# permamote.net
KiCad netlist of a schematic drawn in EAGLE
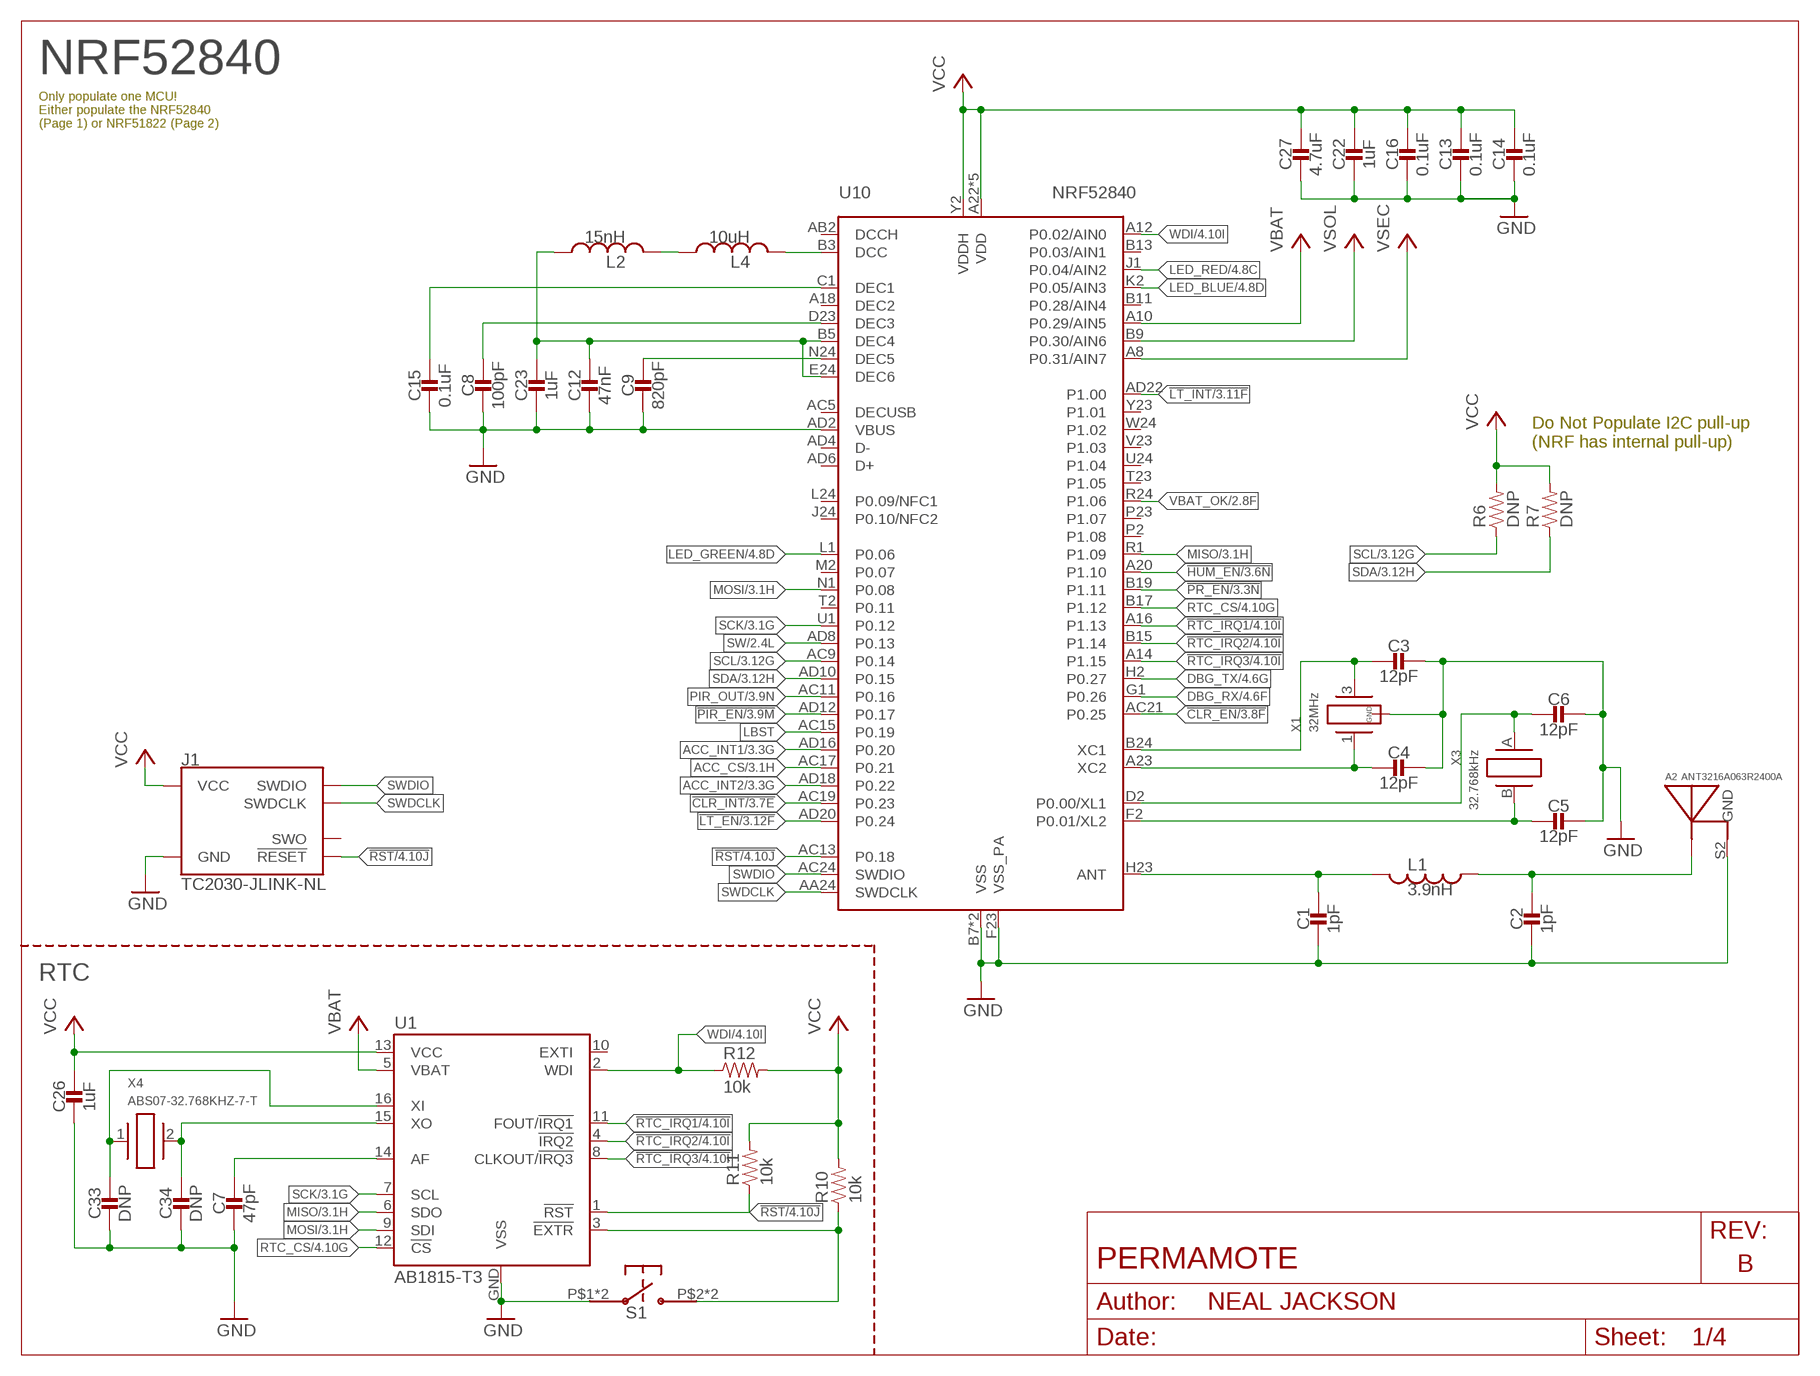
[diagram p0: schematic, sheet 1]
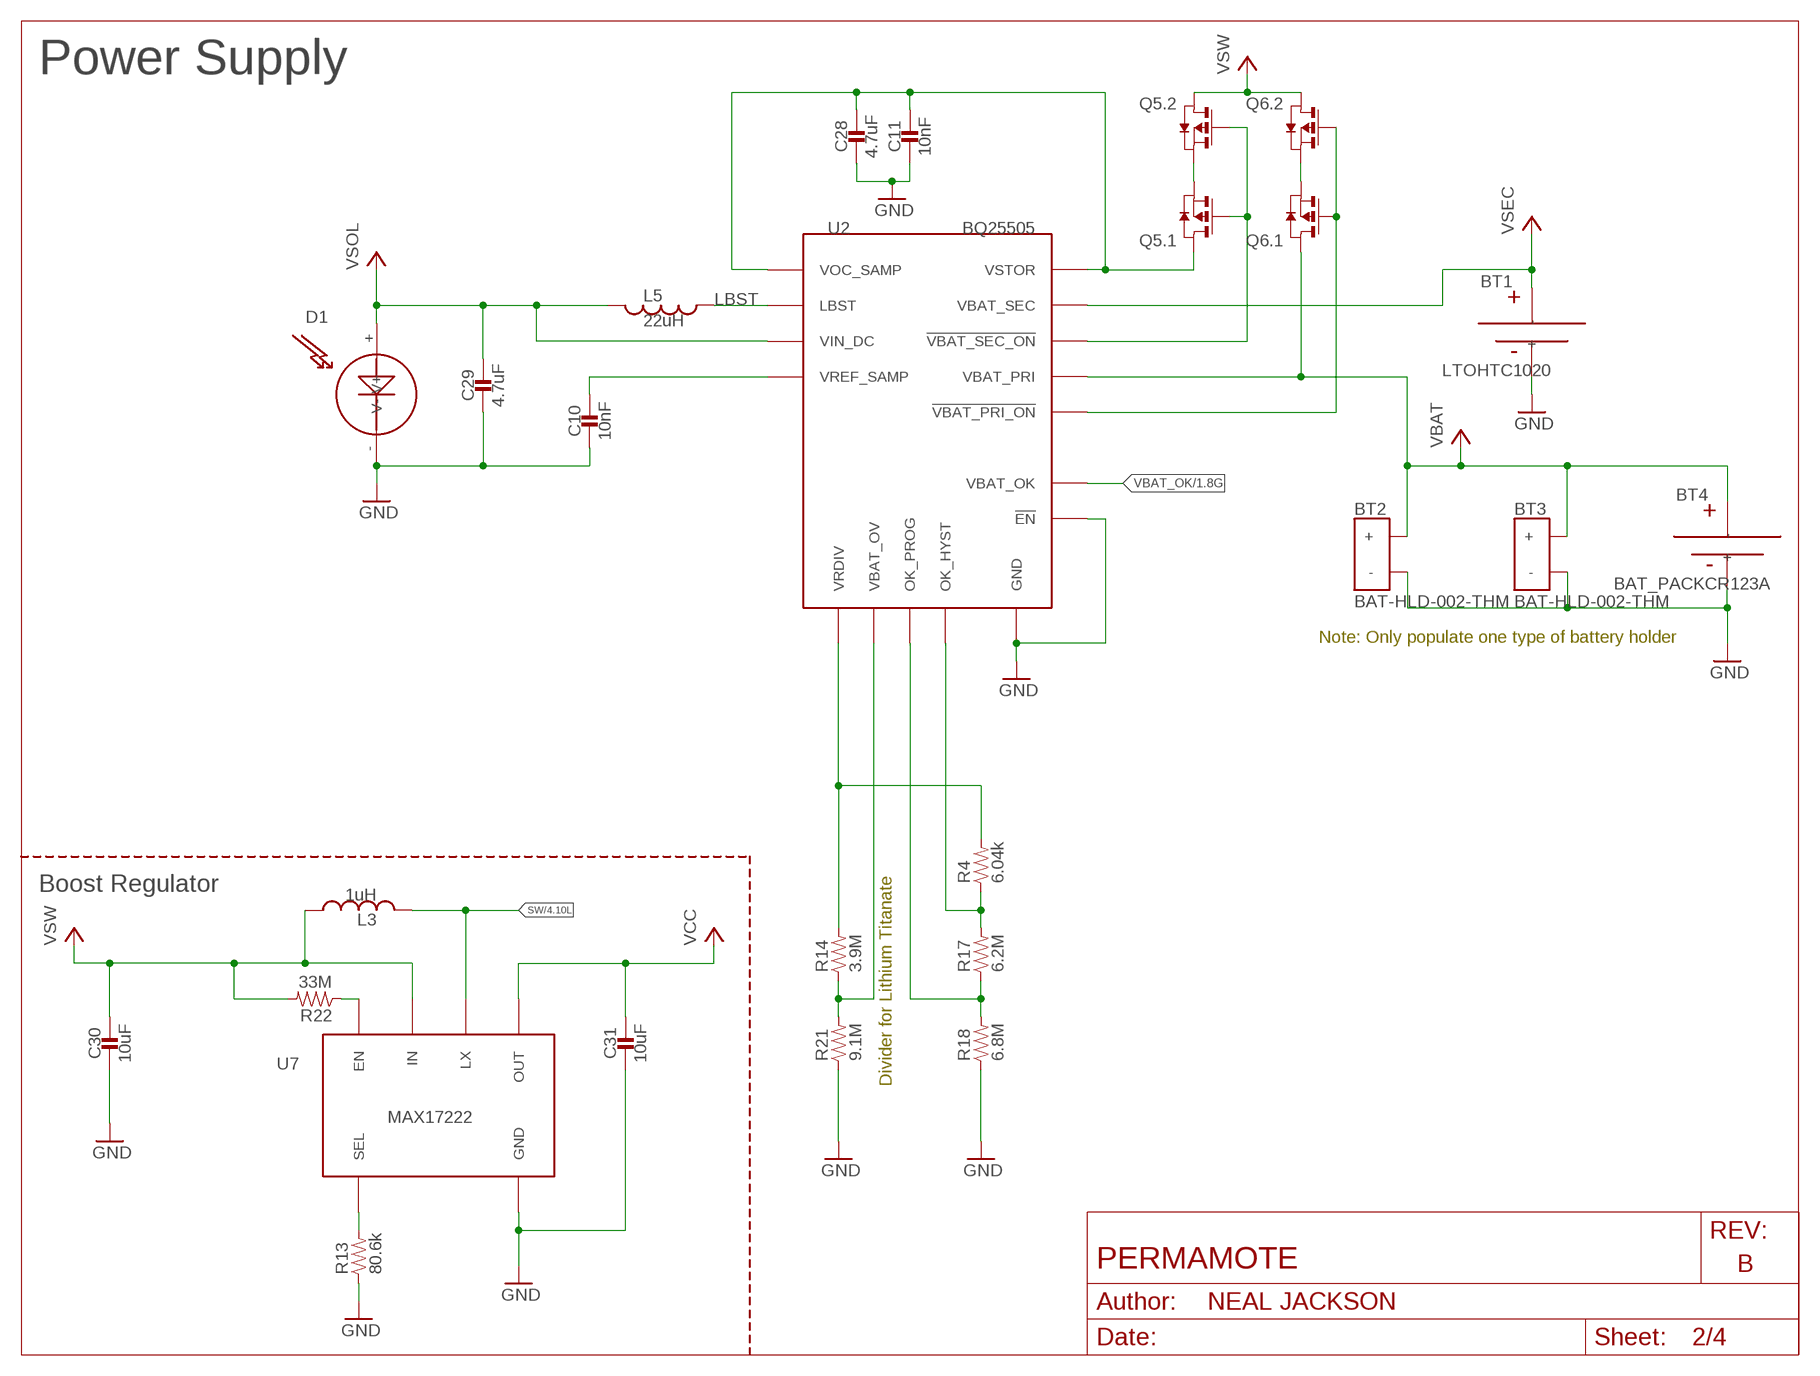
[diagram p1: schematic, sheet 2]
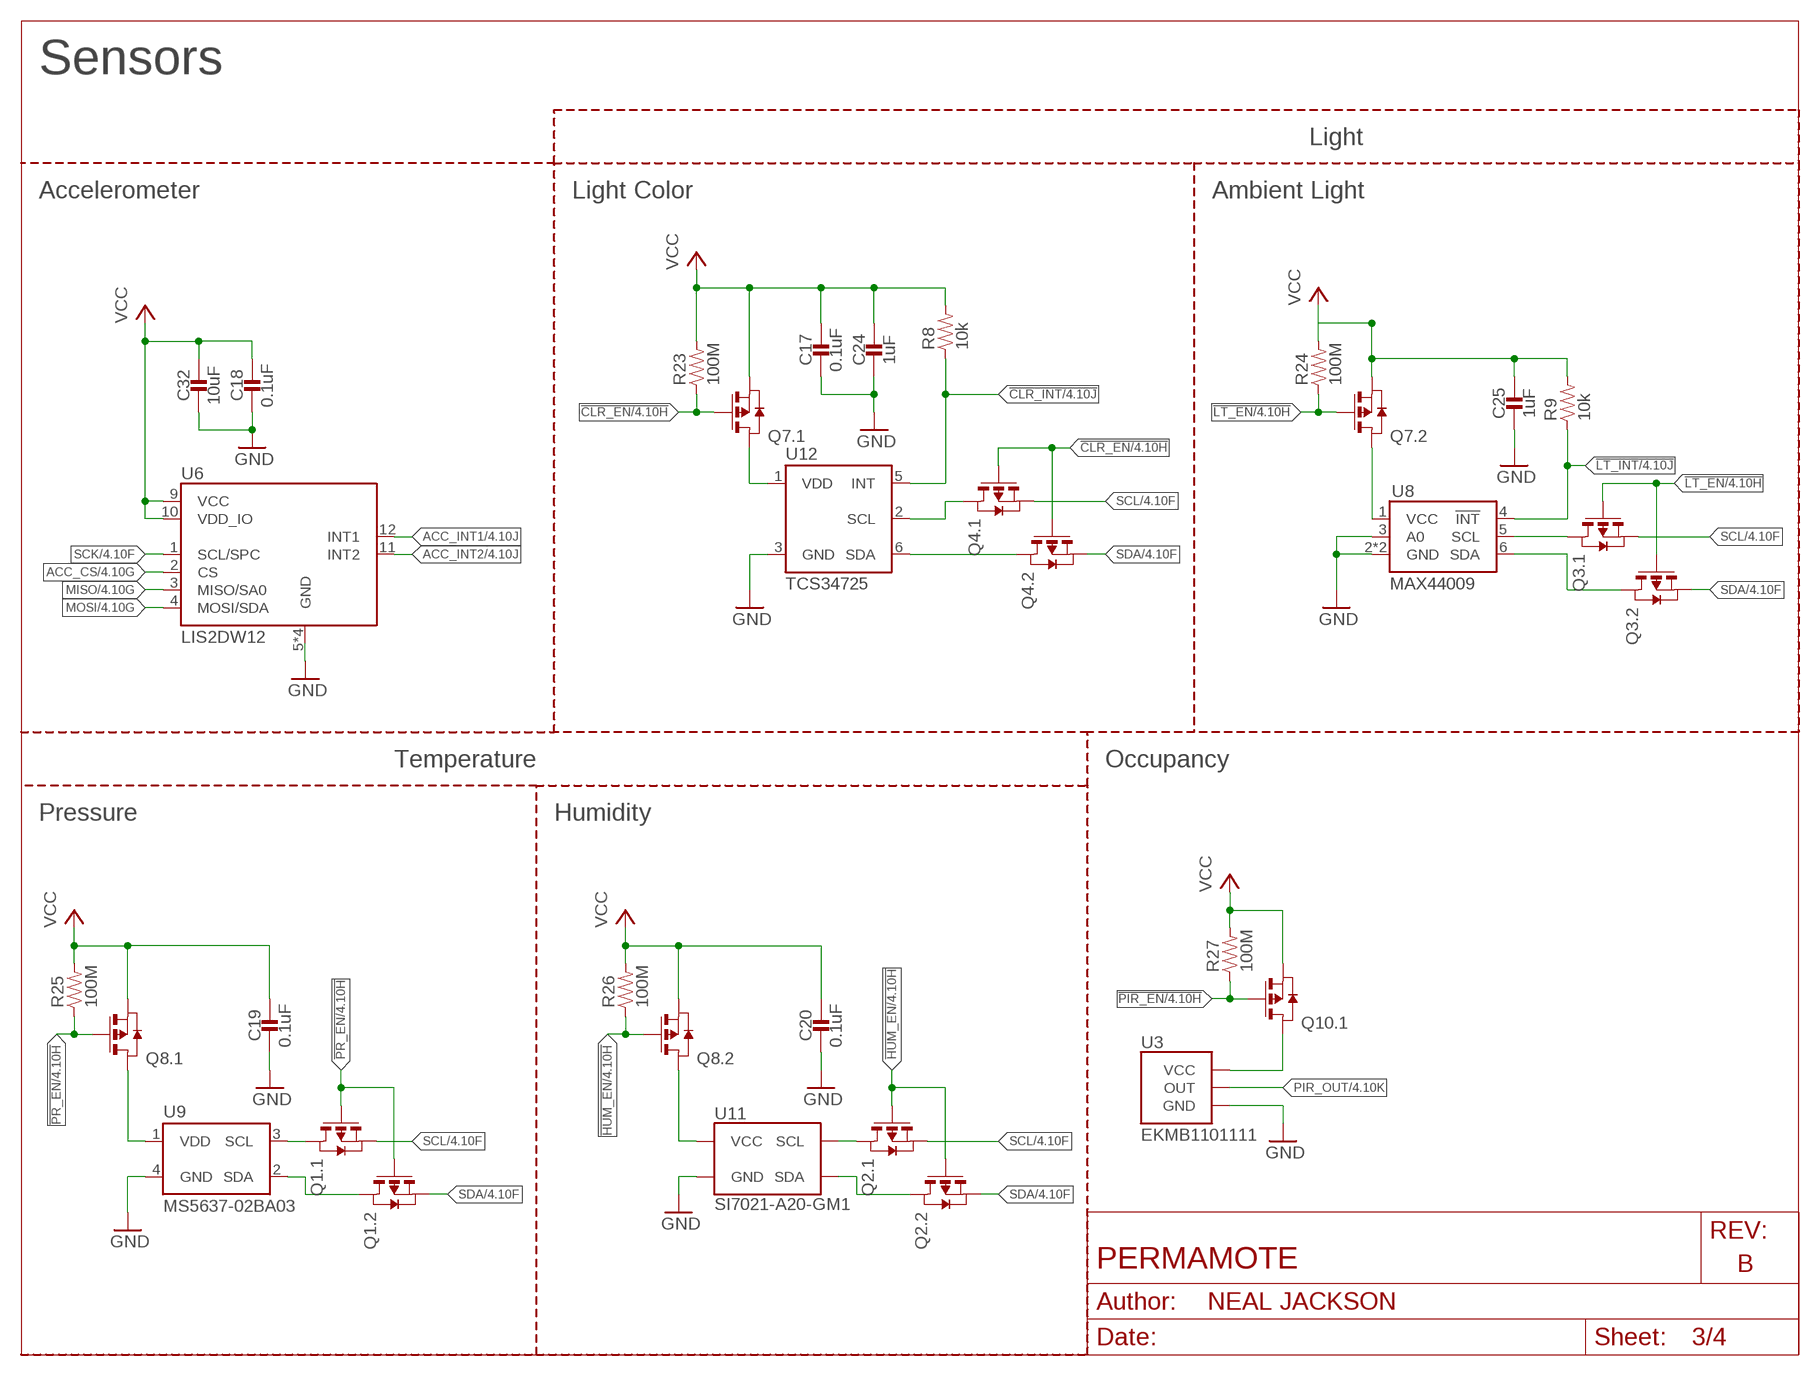
[diagram p2: schematic, sheet 3]
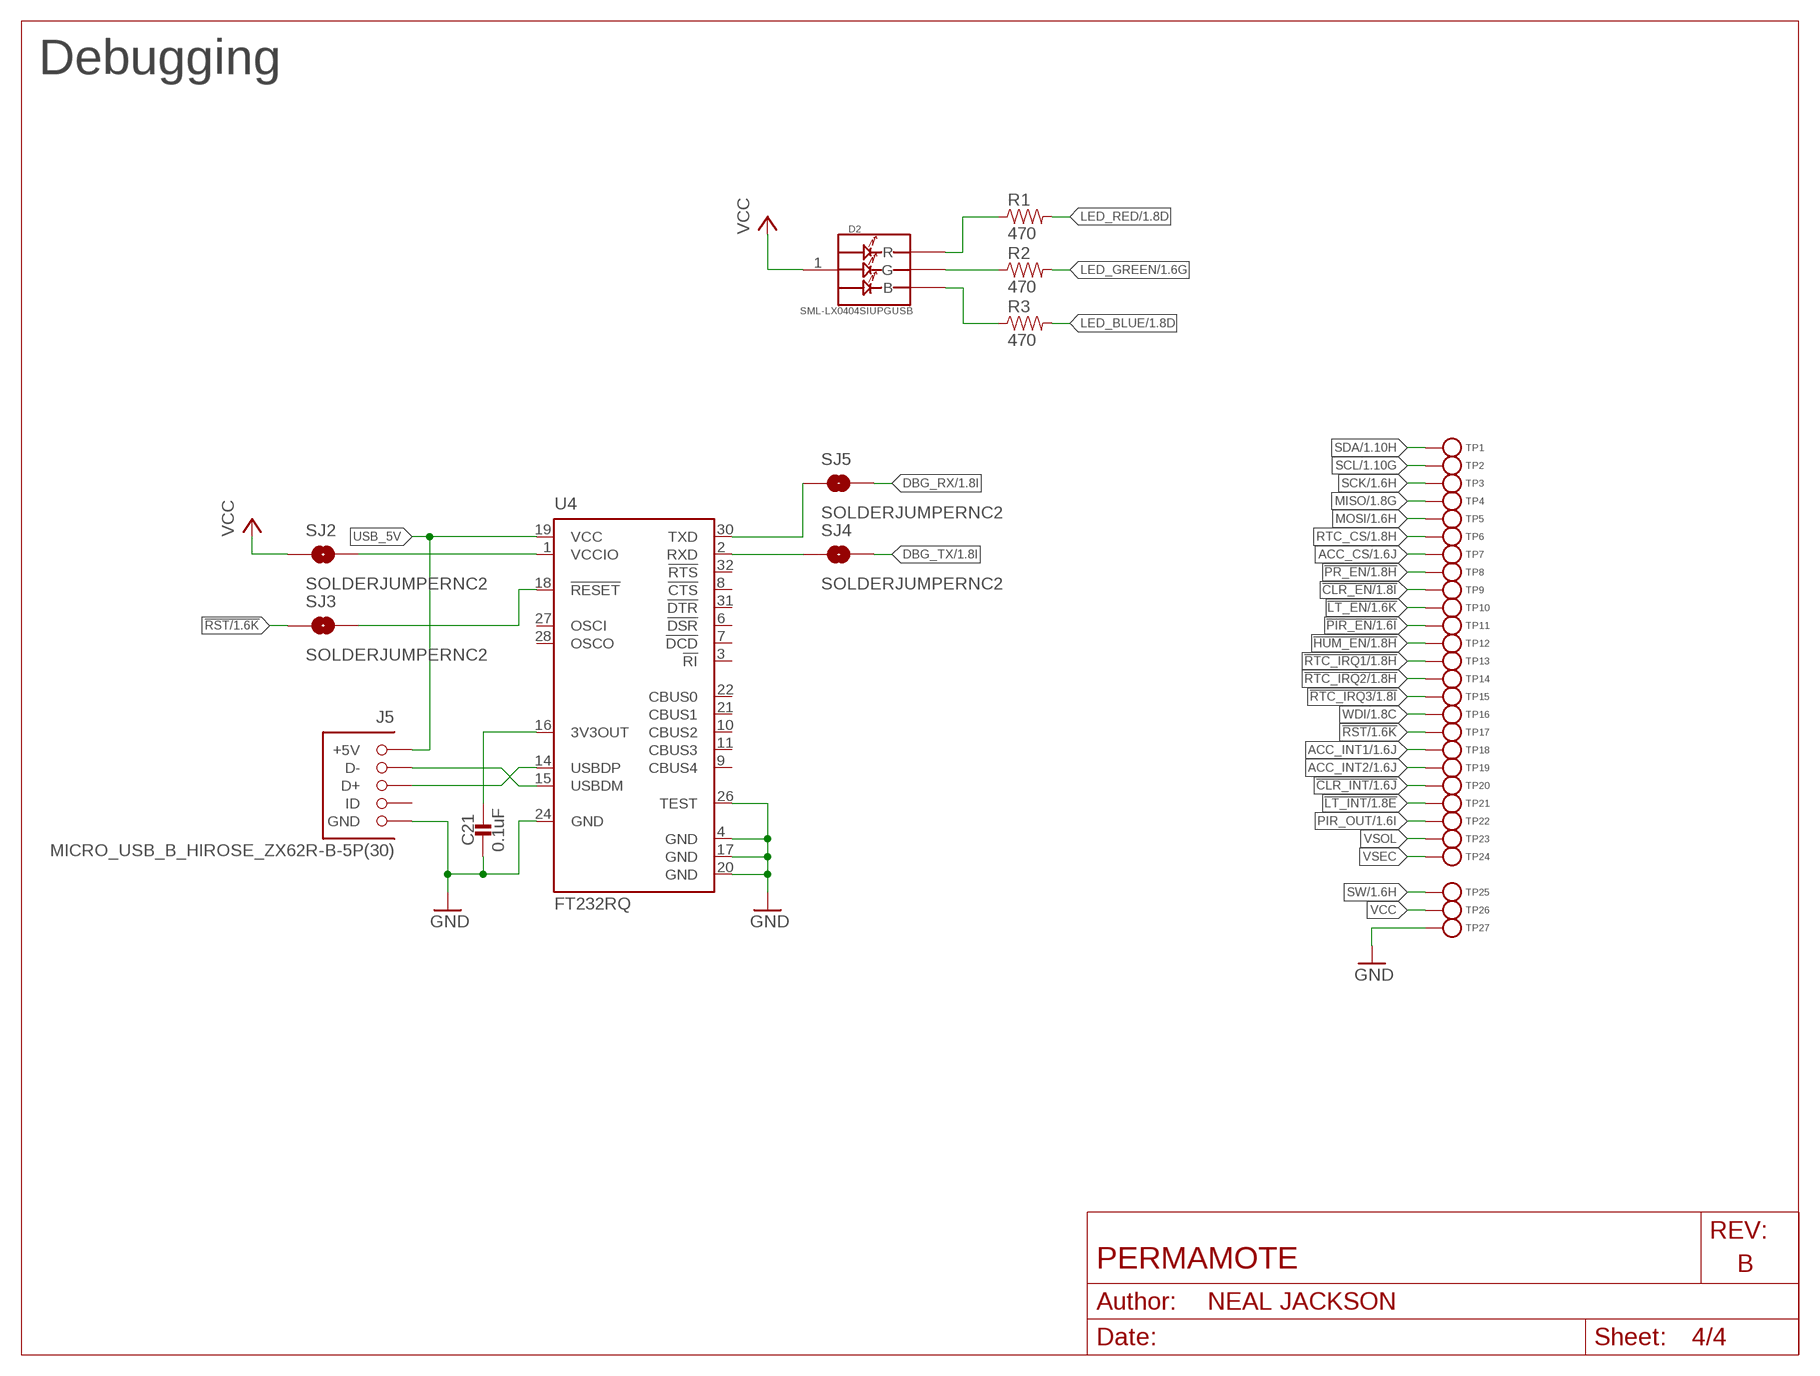
[diagram p3: schematic, sheet 4]

(export (version "E")
  (design (tool "Eeschema 10.0.6"))
  (components
    (comp (ref "A2")
      (value "ANT3216A063R2400A")
      (footprint "eagle-import:ANT3216A063R2400A")
      (fields (field (name "MANUFACTURER") "YAGEO"))
      (libsource (lib "eagle-import") (part "ANT3216A063R2400A"))
    )
    (comp (ref "C1")
      (value "1pF")
      (footprint "eagle-import:0402_CAP")
      (fields (field (name "MPN") "CL05C010CB5NNNC"))
      (libsource (lib "eagle-import") (part "CAPACITOR0402_CAP"))
    )
    (comp (ref "C2")
      (value "1pF")
      (footprint "eagle-import:0402_CAP")
      (fields (field (name "MPN") "CL05C010CB5NNNC"))
      (libsource (lib "eagle-import") (part "CAPACITOR0402_CAP"))
    )
    (comp (ref "C3")
      (value "12pF")
      (footprint "eagle-import:0402_CAP")
      (fields (field (name "MPN") "GRM1555C1H120GA01D "))
      (libsource (lib "eagle-import") (part "CAPACITOR0402_CAP"))
    )
    (comp (ref "C4")
      (value "12pF")
      (footprint "eagle-import:0402_CAP")
      (fields (field (name "MPN") "GRM1555C1H120GA01D "))
      (libsource (lib "eagle-import") (part "CAPACITOR0402_CAP"))
    )
    (comp (ref "C5")
      (value "12pF")
      (footprint "eagle-import:0402_CAP")
      (fields (field (name "MPN") "GRM1555C1H120GA01D "))
      (libsource (lib "eagle-import") (part "CAPACITOR0402_CAP"))
    )
    (comp (ref "C6")
      (value "12pF")
      (footprint "eagle-import:0402_CAP")
      (fields (field (name "MPN") "GRM1555C1H120GA01D "))
      (libsource (lib "eagle-import") (part "CAPACITOR0402_CAP"))
    )
    (comp (ref "C7")
      (value "47pF")
      (footprint "eagle-import:0402_CAP")
      (fields (field (name "MPN") "GRM1555C1H470JA01D "))
      (libsource (lib "eagle-import") (part "CAPACITOR0402_CAP"))
    )
    (comp (ref "C8")
      (value "100pF")
      (footprint "eagle-import:0402_CAP")
      (fields (field (name "MPN") "GRM1555C1H101JA01D "))
      (libsource (lib "eagle-import") (part "CAPACITOR0402_CAP"))
    )
    (comp (ref "C9")
      (value "820pF")
      (footprint "eagle-import:0402_CAP")
      (fields (field (name "MPN") "CL05B821KO5NNNC"))
      (libsource (lib "eagle-import") (part "CAPACITOR0402_CAP"))
    )
    (comp (ref "C12")
      (value "47nF")
      (footprint "eagle-import:0402_CAP")
      (fields (field (name "MPN") "C1005X7R1C473K050BC "))
      (libsource (lib "eagle-import") (part "CAPACITOR0402_CAP"))
    )
    (comp (ref "C13")
      (value "0.1uF")
      (footprint "eagle-import:0402_CAP")
      (fields (field (name "MPN") "GRM155R71C104KA88J "))
      (libsource (lib "eagle-import") (part "CAPACITOR0402_CAP"))
    )
    (comp (ref "C14")
      (value "0.1uF")
      (footprint "eagle-import:0402_CAP")
      (fields (field (name "MPN") "GRM155R71C104KA88J "))
      (libsource (lib "eagle-import") (part "CAPACITOR0402_CAP"))
    )
    (comp (ref "C15")
      (value "0.1uF")
      (footprint "eagle-import:0402_CAP")
      (fields (field (name "MPN") "GRM155R71C104KA88J "))
      (libsource (lib "eagle-import") (part "CAPACITOR0402_CAP"))
    )
    (comp (ref "C16")
      (value "0.1uF")
      (footprint "eagle-import:0402_CAP")
      (fields (field (name "MPN") "GRM155R71C104KA88J "))
      (libsource (lib "eagle-import") (part "CAPACITOR0402_CAP"))
    )
    (comp (ref "C22")
      (value "1uF")
      (footprint "eagle-import:0402_CAP")
      (fields (field (name "MPN") "GRM155R70G105KA12D "))
      (libsource (lib "eagle-import") (part "CAPACITOR0402_CAP"))
    )
    (comp (ref "C23")
      (value "1uF")
      (footprint "eagle-import:0402_CAP")
      (fields (field (name "MPN") "GRM155R70G105KA12D "))
      (libsource (lib "eagle-import") (part "CAPACITOR0402_CAP"))
    )
    (comp (ref "C26")
      (value "1uF")
      (footprint "eagle-import:0402_CAP")
      (fields (field (name "MPN") "GRM155R70G105KA12D "))
      (libsource (lib "eagle-import") (part "CAPACITOR0402_CAP"))
    )
    (comp (ref "C27")
      (value "4.7uF")
      (footprint "eagle-import:0402_CAP")
      (fields (field (name "MPN") "C1005X5R0J475K050BC "))
      (libsource (lib "eagle-import") (part "CAPACITOR0402_CAP"))
    )
    (comp (ref "C33")
      (value "DNP")
      (footprint "eagle-import:0402_CAP")
      (libsource (lib "eagle-import") (part "CAPACITOR0402_CAP"))
    )
    (comp (ref "C34")
      (value "DNP")
      (footprint "eagle-import:0402_CAP")
      (libsource (lib "eagle-import") (part "CAPACITOR0402_CAP"))
    )
    (comp (ref "J1")
      (value "TC2030-JLINK-NL")
      (footprint "eagle-import:TC2030-IDC-NL")
      (libsource (lib "eagle-import") (part "TC2030-JLINK-NL"))
    )
    (comp (ref "L1")
      (value "3.9nH")
      (footprint "eagle-import:0402_CAP")
      (fields (field (name "MPN") "LQP15MN3N9B02D"))
      (libsource (lib "eagle-import") (part "INDUCTOR0402"))
    )
    (comp (ref "L2")
      (value "15nH")
      (footprint "eagle-import:0402_CAP")
      (fields (field (name "MPN") "HK100515NJ-T "))
      (libsource (lib "eagle-import") (part "INDUCTOR0402"))
    )
    (comp (ref "L4")
      (value "10uH")
      (footprint "eagle-import:0603_CAP")
      (fields (field (name "MPN") "LQM18FN100M00D "))
      (libsource (lib "eagle-import") (part "INDUCTOR0603"))
    )
    (comp (ref "R6")
      (value "DNP")
      (footprint "eagle-import:0402_RES")
      (fields (field (name "MPN") "RC0402JR-0710KL"))
      (libsource (lib "eagle-import") (part "RESISTOR0402_RES"))
    )
    (comp (ref "R7")
      (value "DNP")
      (footprint "eagle-import:0402_RES")
      (fields (field (name "MPN") "RC0402JR-0710KL"))
      (libsource (lib "eagle-import") (part "RESISTOR0402_RES"))
    )
    (comp (ref "R10")
      (value "10k")
      (footprint "eagle-import:0402_RES")
      (fields (field (name "MPN") "RC0402JR-0710KL"))
      (libsource (lib "eagle-import") (part "RESISTOR0402_RES"))
    )
    (comp (ref "R11")
      (value "10k")
      (footprint "eagle-import:0402_RES")
      (fields (field (name "MPN") "RC0402JR-0710KL"))
      (libsource (lib "eagle-import") (part "RESISTOR0402_RES"))
    )
    (comp (ref "R12")
      (value "10k")
      (footprint "eagle-import:0402_RES")
      (fields (field (name "MPN") "RC0402JR-0710KL"))
      (libsource (lib "eagle-import") (part "RESISTOR0402_RES"))
    )
    (comp (ref "S1")
      (value "EVQP2")
      (footprint "eagle-import:EVQP2")
      (fields (field (name "MPN") "EVQ-P2K02Q "))
      (libsource (lib "eagle-import") (part "EVQP2"))
    )
    (comp (ref "U1")
      (value "AB1815-T3")
      (footprint "eagle-import:QFN-16-3MM")
      (fields (field (name "MANUFACTURER") "Abracon"))
      (libsource (lib "eagle-import") (part "AB1815-T3"))
    )
    (comp (ref "U10")
      (value "NRF52840")
      (footprint "eagle-import:AQFN73")
      (fields (field (name "MANUFACTURER") "NORIDIC SEMICONDUCTOR"))
      (libsource (lib "eagle-import") (part "NRF52840"))
    )
    (comp (ref "X1")
      (value "32MHz")
      (footprint "eagle-import:TXC-7V")
      (fields (field (name "MANUFACTURER") "TXC CORPORATION") (field (name "MPN") "7M-32.000MAHV-T"))
      (libsource (lib "eagle-import") (part "7V-32.000MAHV-T"))
    )
    (comp (ref "X3")
      (value "32.768kHz")
      (footprint "eagle-import:ABS05")
      (fields (field (name "MANUFACTURER") "Abracon") (field (name "MPN") "ABS05-32.768KHZ-9-T"))
      (libsource (lib "eagle-import") (part "ABS05-32.768KHZ-9-T"))
    )
    (comp (ref "X4")
      (value "ABS07-32.768KHZ-7-T")
      (footprint "eagle-import:2-SMD")
      (fields (field (name "MANUFACTURER") "ABRACON") (field (name "MPN") "ABS07-32.768KHZ-7-T "))
      (libsource (lib "eagle-import") (part "ABS07-32.768KHZ-7-T"))
    )
    (comp (ref "BT1")
      (value "LTOHTC1020")
      (footprint "eagle-import:1020")
      (libsource (lib "eagle-import") (part "LTOHTC1020"))
    )
    (comp (ref "BT2")
      (value "BAT-HLD-002-THM")
      (footprint "eagle-import:BAT-HLD-002-THM")
      (fields
        (field (name "DIGIKEY") "BAT-HLD-001-THM-ND")
        (field (name "MOUSER") "712-BAT-HLD-001-THM")
        (field (name "MPN") "BAT-HLD-001-THM")
      )
      (libsource (lib "eagle-import") (part "BAT-HLD-002-THM"))
    )
    (comp (ref "BT3")
      (value "BAT-HLD-002-THM")
      (footprint "eagle-import:BAT-HLD-002-THM")
      (fields
        (field (name "DIGIKEY") "BAT-HLD-001-THM-ND")
        (field (name "MOUSER") "712-BAT-HLD-001-THM")
        (field (name "MPN") "BAT-HLD-001-THM")
      )
      (libsource (lib "eagle-import") (part "BAT-HLD-002-THM"))
    )
    (comp (ref "BT4")
      (value "BAT_PACKCR123A")
      (footprint "eagle-import:BH123A")
      (fields (field (name "MANUFACTURER") "MPD") (field (name "MPN") "BH123A"))
      (libsource (lib "eagle-import") (part "BAT_PACKCR123A"))
    )
    (comp (ref "C10")
      (value "10nF")
      (footprint "eagle-import:0402_CAP")
      (fields (field (name "MPN") "GRM155R71H103KA88D "))
      (libsource (lib "eagle-import") (part "CAPACITOR0402_CAP"))
    )
    (comp (ref "C11")
      (value "10nF")
      (footprint "eagle-import:0402_CAP")
      (fields (field (name "MPN") "GRM155R71H103KA88D "))
      (libsource (lib "eagle-import") (part "CAPACITOR0402_CAP"))
    )
    (comp (ref "C28")
      (value "4.7uF")
      (footprint "eagle-import:0402_CAP")
      (fields (field (name "MPN") "C1005X5R0J475K050BC "))
      (libsource (lib "eagle-import") (part "CAPACITOR0402_CAP"))
    )
    (comp (ref "C29")
      (value "4.7uF")
      (footprint "eagle-import:0402_CAP")
      (fields (field (name "MPN") "C1005X5R0J475K050BC "))
      (libsource (lib "eagle-import") (part "CAPACITOR0402_CAP"))
    )
    (comp (ref "C30")
      (value "10uF")
      (footprint "eagle-import:0603_CAP")
      (fields (field (name "MPN") "GRM188R60J106ME47D "))
      (libsource (lib "eagle-import") (part "CAPACITOR0603_CAP"))
    )
    (comp (ref "C31")
      (value "10uF")
      (footprint "eagle-import:0603_CAP")
      (fields (field (name "MPN") "GRM188R60J106ME47D "))
      (libsource (lib "eagle-import") (part "CAPACITOR0603_CAP"))
    )
    (comp (ref "D1")
      (value "SOLARCELLHOLES")
      (footprint "eagle-import:SOLAR_HOLES")
      (fields (field (name "MPN") "AM-1454CA"))
      (libsource (lib "eagle-import") (part "SOLARCELLHOLES"))
    )
    (comp (ref "L3")
      (value "1uH")
      (footprint "eagle-import:IHL-1212BZ-11")
      (fields
        (field (name "MANUFACTURER") "Vishay Dale")
        (field (name "MPN") "IHLP1212BZER2R2M11")
        (field (name "DIGIKEY") "541-1319-1-ND")
        (field (name "MPN_1") "IHLP1212BZER1R0M11")
      )
      (libsource (lib "eagle-import") (part "INDUCTORIHL"))
    )
    (comp (ref "L5")
      (value "22uH")
      (footprint "eagle-import:74437324220")
      (fields (field (name "DIGIKEY") "732-3340-1-ND") (field (name "MPN") "74437324220 "))
      (libsource (lib "eagle-import") (part "INDUCTOR74437324220"))
    )
    (comp (ref "Q5")
      (value "PMDXB950UPEL")
      (footprint "eagle-import:XDFN-6")
      (fields (field (name "MANUFACTURER") "NEXPERIA") (field (name "MPN") "PMDXB950UPELZ"))
      (libsource (lib "eagle-import") (part "PMDXB950UPEL"))
    )
    (comp (ref "Q6")
      (value "PMDXB950UPEL")
      (footprint "eagle-import:XDFN-6")
      (fields (field (name "MANUFACTURER") "NEXPERIA") (field (name "MPN") "PMDXB950UPELZ"))
      (libsource (lib "eagle-import") (part "PMDXB950UPEL"))
    )
    (comp (ref "R4")
      (value "6.04k")
      (footprint "eagle-import:0402_RES")
      (fields (field (name "MPN") "RC0402FR-076K04L"))
      (libsource (lib "eagle-import") (part "RESISTOR0402_RES"))
    )
    (comp (ref "R13")
      (value "80.6k")
      (footprint "eagle-import:0603-RES")
      (fields (field (name "MPN") "RC0603FR-0780K6L "))
      (libsource (lib "eagle-import") (part "RESISTOR0603_RES"))
    )
    (comp (ref "R14")
      (value "3.9M")
      (footprint "eagle-import:0402_RES")
      (fields (field (name "MPN") "RC0402JR-073M9L"))
      (libsource (lib "eagle-import") (part "RESISTOR0402_RES"))
    )
    (comp (ref "R17")
      (value "6.2M")
      (footprint "eagle-import:0402_RES")
      (fields (field (name "MPN") "RC0402JR-076M2L"))
      (libsource (lib "eagle-import") (part "RESISTOR0402_RES"))
    )
    (comp (ref "R18")
      (value "6.8M")
      (footprint "eagle-import:0402_RES")
      (fields (field (name "MPN") "RC0402JR-076M8L"))
      (libsource (lib "eagle-import") (part "RESISTOR0402_RES"))
    )
    (comp (ref "R21")
      (value "9.1M")
      (footprint "eagle-import:0402_RES")
      (fields (field (name "MPN") "RC0402JR-079M1L"))
      (libsource (lib "eagle-import") (part "RESISTOR0402_RES"))
    )
    (comp (ref "R22")
      (value "33M")
      (footprint "eagle-import:0603-RES")
      (fields (field (name "MPN") "HMC0603JT33M0 "))
      (libsource (lib "eagle-import") (part "RESISTOR0603_RES"))
    )
    (comp (ref "U2")
      (value "BQ25505")
      (footprint "eagle-import:S-PVQFN-N20-RGR")
      (fields (field (name "MANUFACTURER") "TI") (field (name "MPN") "BQ25505RGRR"))
      (libsource (lib "eagle-import") (part "BQ25505"))
    )
    (comp (ref "U7")
      (value "MAX17222")
      (footprint "eagle-import:UDFN-6-MAXIM")
      (fields (field (name "MANUFACTURER") "MAXIM INTEGRATED") (field (name "MPN") "MAX17222ELT+T"))
      (libsource (lib "eagle-import") (part "MAX17222"))
    )
    (comp (ref "C17")
      (value "0.1uF")
      (footprint "eagle-import:0402_CAP")
      (fields (field (name "MPN") "GRM155R71C104KA88J "))
      (libsource (lib "eagle-import") (part "CAPACITOR0402_CAP"))
    )
    (comp (ref "C18")
      (value "0.1uF")
      (footprint "eagle-import:0402_CAP")
      (fields (field (name "MPN") "GRM155R71C104KA88J "))
      (libsource (lib "eagle-import") (part "CAPACITOR0402_CAP"))
    )
    (comp (ref "C19")
      (value "0.1uF")
      (footprint "eagle-import:0402_CAP")
      (fields (field (name "MPN") "GRM155R71C104KA88J "))
      (libsource (lib "eagle-import") (part "CAPACITOR0402_CAP"))
    )
    (comp (ref "C20")
      (value "0.1uF")
      (footprint "eagle-import:0402_CAP")
      (fields (field (name "MPN") "GRM155R71C104KA88J "))
      (libsource (lib "eagle-import") (part "CAPACITOR0402_CAP"))
    )
    (comp (ref "C24")
      (value "1uF")
      (footprint "eagle-import:0402_CAP")
      (fields (field (name "MPN") "GRM155R70G105KA12D "))
      (libsource (lib "eagle-import") (part "CAPACITOR0402_CAP"))
    )
    (comp (ref "C25")
      (value "1uF")
      (footprint "eagle-import:0402_CAP")
      (fields (field (name "MPN") "GRM155R70G105KA12D "))
      (libsource (lib "eagle-import") (part "CAPACITOR0402_CAP"))
    )
    (comp (ref "C32")
      (value "10uF")
      (footprint "eagle-import:0603_CAP")
      (fields (field (name "MPN") "GRM188R60J106ME47D "))
      (libsource (lib "eagle-import") (part "CAPACITOR0603_CAP"))
    )
    (comp (ref "Q1")
      (value "PMDXB950UPEL")
      (footprint "eagle-import:XDFN-6")
      (fields (field (name "MANUFACTURER") "NEXPERIA") (field (name "MPN") "PMDXB950UPELZ"))
      (libsource (lib "eagle-import") (part "PMDXB950UPEL"))
    )
    (comp (ref "Q2")
      (value "PMDXB950UPEL")
      (footprint "eagle-import:XDFN-6")
      (fields (field (name "MANUFACTURER") "NEXPERIA") (field (name "MPN") "PMDXB950UPELZ"))
      (libsource (lib "eagle-import") (part "PMDXB950UPEL"))
    )
    (comp (ref "Q3")
      (value "PMDXB950UPEL")
      (footprint "eagle-import:XDFN-6")
      (fields (field (name "MANUFACTURER") "NEXPERIA") (field (name "MPN") "PMDXB950UPELZ"))
      (libsource (lib "eagle-import") (part "PMDXB950UPEL"))
    )
    (comp (ref "Q4")
      (value "PMDXB950UPEL")
      (footprint "eagle-import:XDFN-6")
      (fields (field (name "MANUFACTURER") "NEXPERIA") (field (name "MPN") "PMDXB950UPELZ"))
      (libsource (lib "eagle-import") (part "PMDXB950UPEL"))
    )
    (comp (ref "Q7")
      (value "PMDXB950UPEL")
      (footprint "eagle-import:XDFN-6")
      (fields (field (name "MANUFACTURER") "NEXPERIA") (field (name "MPN") "PMDXB950UPELZ"))
      (libsource (lib "eagle-import") (part "PMDXB950UPEL"))
    )
    (comp (ref "Q8")
      (value "PMDXB950UPEL")
      (footprint "eagle-import:XDFN-6")
      (fields (field (name "MANUFACTURER") "NEXPERIA") (field (name "MPN") "PMDXB950UPELZ"))
      (libsource (lib "eagle-import") (part "PMDXB950UPEL"))
    )
    (comp (ref "Q10")
      (value "PMDXB950UPEL")
      (footprint "eagle-import:XDFN-6")
      (fields (field (name "MANUFACTURER") "NEXPERIA") (field (name "MPN") "PMDXB950UPELZ"))
      (libsource (lib "eagle-import") (part "PMDXB950UPEL"))
    )
    (comp (ref "R8")
      (value "10k")
      (footprint "eagle-import:0402_RES")
      (fields (field (name "MPN") "RC0402JR-0710KL"))
      (libsource (lib "eagle-import") (part "RESISTOR0402_RES"))
    )
    (comp (ref "R9")
      (value "10k")
      (footprint "eagle-import:0402_RES")
      (fields (field (name "MPN") "RC0402JR-0710KL"))
      (libsource (lib "eagle-import") (part "RESISTOR0402_RES"))
    )
    (comp (ref "R23")
      (value "100M")
      (footprint "eagle-import:0402_RES")
      (fields (field (name "MPN") "HMC0402JT100M "))
      (libsource (lib "eagle-import") (part "RESISTOR0402_RES"))
    )
    (comp (ref "R24")
      (value "100M")
      (footprint "eagle-import:0402_RES")
      (fields (field (name "MPN") "HMC0402JT100M "))
      (libsource (lib "eagle-import") (part "RESISTOR0402_RES"))
    )
    (comp (ref "R25")
      (value "100M")
      (footprint "eagle-import:0402_RES")
      (fields (field (name "MPN") "HMC0402JT100M "))
      (libsource (lib "eagle-import") (part "RESISTOR0402_RES"))
    )
    (comp (ref "R26")
      (value "100M")
      (footprint "eagle-import:0402_RES")
      (fields (field (name "MPN") "HMC0402JT100M "))
      (libsource (lib "eagle-import") (part "RESISTOR0402_RES"))
    )
    (comp (ref "R27")
      (value "100M")
      (footprint "eagle-import:0402_RES")
      (fields (field (name "MPN") "HMC0402JT100M "))
      (libsource (lib "eagle-import") (part "RESISTOR0402_RES"))
    )
    (comp (ref "U3")
      (value "EKMB1101111")
      (footprint "eagle-import:AMN2")
      (fields (field (name "MANUFACTURER") "PANASONIC"))
      (libsource (lib "eagle-import") (part "EKMB1101111"))
    )
    (comp (ref "U6")
      (value "LIS2DW12")
      (footprint "eagle-import:LGA-12")
      (fields (field (name "MANUFACTURER") "STMicroelectronics") (field (name "MPN") "LIS2DW12TR"))
      (libsource (lib "eagle-import") (part "LIS2DW12"))
    )
    (comp (ref "U8")
      (value "MAX44009")
      (footprint "eagle-import:UDFN-6-EXPOSED")
      (fields (field (name "MANUFACTURER") "MAXIM") (field (name "MPN") "MAX44009EDT+T"))
      (libsource (lib "eagle-import") (part "MAX44009"))
    )
    (comp (ref "U9")
      (value "MS5637-02BA03")
      (footprint "eagle-import:4-SMD")
      (fields (field (name "MANUFACTURER") "TE CONNECTIVITY") (field (name "MPN") "MS563702BA03-50"))
      (libsource (lib "eagle-import") (part "MS5637-02BA03"))
    )
    (comp (ref "U11")
      (value "SI7021-A20-GM1")
      (footprint "eagle-import:DFN-6_3MM")
      (fields (field (name "MPN") "SI7021-A20-GM1 "))
      (libsource (lib "eagle-import") (part "SI7021-A20-GM1"))
    )
    (comp (ref "U12")
      (value "TCS34725")
      (footprint "eagle-import:FN-6")
      (fields (field (name "MPN") "TCS34725FN"))
      (libsource (lib "eagle-import") (part "TCS34725"))
    )
    (comp (ref "C21")
      (value "0.1uF")
      (footprint "eagle-import:0402_CAP")
      (fields (field (name "MPN") "GRM155R71C104KA88J "))
      (libsource (lib "eagle-import") (part "CAPACITOR0402_CAP"))
    )
    (comp (ref "D2")
      (value "SML-LX0404SIUPGUSB")
      (footprint "eagle-import:1MM_SQ_4PAD")
      (fields (field (name "MANUFACTURER") "Lumex Opto"))
      (libsource (lib "eagle-import") (part "SML-LX0404SIUPGUSB"))
    )
    (comp (ref "J5")
      (value "MICRO_USB_B_HIROSE_ZX62R-B-5P(30)")
      (footprint "eagle-import:MICRO_USB_B_HIROSE_ZX62R-B-5P(30)")
      (fields (field (name "MPN") "ZX62R-B-5P(30)"))
      (libsource (lib "eagle-import") (part "MICRO_USB_B_HIROSE_ZX62R-B-5P(30)"))
    )
    (comp (ref "R1")
      (value "470")
      (footprint "eagle-import:0402_RES")
      (fields (field (name "MPN") "RC0402JR-07470RL "))
      (libsource (lib "eagle-import") (part "RESISTOR0402_RES"))
    )
    (comp (ref "R2")
      (value "470")
      (footprint "eagle-import:0402_RES")
      (fields (field (name "MPN") "RC0402JR-07470RL "))
      (libsource (lib "eagle-import") (part "RESISTOR0402_RES"))
    )
    (comp (ref "R3")
      (value "470")
      (footprint "eagle-import:0402_RES")
      (fields (field (name "MPN") "RC0402JR-07470RL "))
      (libsource (lib "eagle-import") (part "RESISTOR0402_RES"))
    )
    (comp (ref "SJ2")
      (value "SOLDERJUMPERNC2")
      (footprint "eagle-import:SJ_2S-NOTRACE")
      (libsource (lib "eagle-import") (part "SOLDERJUMPERNC2"))
    )
    (comp (ref "SJ3")
      (value "SOLDERJUMPERNC2")
      (footprint "eagle-import:SJ_2S-NOTRACE")
      (libsource (lib "eagle-import") (part "SOLDERJUMPERNC2"))
    )
    (comp (ref "SJ4")
      (value "SOLDERJUMPERNC2")
      (footprint "eagle-import:SJ_2S-NOTRACE")
      (libsource (lib "eagle-import") (part "SOLDERJUMPERNC2"))
    )
    (comp (ref "SJ5")
      (value "SOLDERJUMPERNC2")
      (footprint "eagle-import:SJ_2S-NOTRACE")
      (libsource (lib "eagle-import") (part "SOLDERJUMPERNC2"))
    )
    (comp (ref "TP1")
      (value "TEST-POINT")
      (footprint "eagle-import:PAD.03X.03")
      (libsource (lib "eagle-import") (part "TEST-POINT"))
    )
    (comp (ref "TP2")
      (value "TEST-POINT")
      (footprint "eagle-import:PAD.03X.03")
      (libsource (lib "eagle-import") (part "TEST-POINT"))
    )
    (comp (ref "TP3")
      (value "TEST-POINT")
      (footprint "eagle-import:PAD.03X.03")
      (libsource (lib "eagle-import") (part "TEST-POINT"))
    )
    (comp (ref "TP4")
      (value "TEST-POINT")
      (footprint "eagle-import:PAD.03X.03")
      (libsource (lib "eagle-import") (part "TEST-POINT"))
    )
    (comp (ref "TP5")
      (value "TEST-POINT")
      (footprint "eagle-import:PAD.03X.03")
      (libsource (lib "eagle-import") (part "TEST-POINT"))
    )
    (comp (ref "TP6")
      (value "TEST-POINT")
      (footprint "eagle-import:PAD.03X.03")
      (libsource (lib "eagle-import") (part "TEST-POINT"))
    )
    (comp (ref "TP7")
      (value "TEST-POINT")
      (footprint "eagle-import:PAD.03X.03")
      (libsource (lib "eagle-import") (part "TEST-POINT"))
    )
    (comp (ref "TP8")
      (value "TEST-POINT")
      (footprint "eagle-import:PAD.03X.03")
      (libsource (lib "eagle-import") (part "TEST-POINT"))
    )
    (comp (ref "TP9")
      (value "TEST-POINT")
      (footprint "eagle-import:PAD.03X.03")
      (libsource (lib "eagle-import") (part "TEST-POINT"))
    )
    (comp (ref "TP10")
      (value "TEST-POINT")
      (footprint "eagle-import:PAD.03X.03")
      (libsource (lib "eagle-import") (part "TEST-POINT"))
    )
    (comp (ref "TP11")
      (value "TEST-POINT")
      (footprint "eagle-import:PAD.03X.03")
      (libsource (lib "eagle-import") (part "TEST-POINT"))
    )
    (comp (ref "TP12")
      (value "TEST-POINT")
      (footprint "eagle-import:PAD.03X.03")
      (libsource (lib "eagle-import") (part "TEST-POINT"))
    )
    (comp (ref "TP13")
      (value "TEST-POINT")
      (footprint "eagle-import:PAD.03X.03")
      (libsource (lib "eagle-import") (part "TEST-POINT"))
    )
    (comp (ref "TP14")
      (value "TEST-POINT")
      (footprint "eagle-import:PAD.03X.03")
      (libsource (lib "eagle-import") (part "TEST-POINT"))
    )
    (comp (ref "TP15")
      (value "TEST-POINT")
      (footprint "eagle-import:PAD.03X.03")
      (libsource (lib "eagle-import") (part "TEST-POINT"))
    )
    (comp (ref "TP16")
      (value "TEST-POINT")
      (footprint "eagle-import:PAD.03X.03")
      (libsource (lib "eagle-import") (part "TEST-POINT"))
    )
    (comp (ref "TP17")
      (value "TEST-POINT")
      (footprint "eagle-import:PAD.03X.03")
      (libsource (lib "eagle-import") (part "TEST-POINT"))
    )
    (comp (ref "TP18")
      (value "TEST-POINT")
      (footprint "eagle-import:PAD.03X.03")
      (libsource (lib "eagle-import") (part "TEST-POINT"))
    )
    (comp (ref "TP19")
      (value "TEST-POINT")
      (footprint "eagle-import:PAD.03X.03")
      (libsource (lib "eagle-import") (part "TEST-POINT"))
    )
    (comp (ref "TP20")
      (value "TEST-POINT")
      (footprint "eagle-import:PAD.03X.03")
      (libsource (lib "eagle-import") (part "TEST-POINT"))
    )
    (comp (ref "TP21")
      (value "TEST-POINT")
      (footprint "eagle-import:PAD.03X.03")
      (libsource (lib "eagle-import") (part "TEST-POINT"))
    )
    (comp (ref "TP22")
      (value "TEST-POINT")
      (footprint "eagle-import:PAD.03X.03")
      (libsource (lib "eagle-import") (part "TEST-POINT"))
    )
    (comp (ref "TP23")
      (value "TEST-POINT")
      (footprint "eagle-import:PAD.03X.03")
      (libsource (lib "eagle-import") (part "TEST-POINT"))
    )
    (comp (ref "TP24")
      (value "TEST-POINT")
      (footprint "eagle-import:PAD.03X.03")
      (libsource (lib "eagle-import") (part "TEST-POINT"))
    )
    (comp (ref "TP25")
      (value "TEST-POINT")
      (footprint "eagle-import:PAD.03X.03")
      (libsource (lib "eagle-import") (part "TEST-POINT"))
    )
    (comp (ref "TP26")
      (value "TEST-POINT")
      (footprint "eagle-import:PAD.03X.03")
      (libsource (lib "eagle-import") (part "TEST-POINT"))
    )
    (comp (ref "TP27")
      (value "TEST-POINT")
      (footprint "eagle-import:PAD.03X.03")
      (libsource (lib "eagle-import") (part "TEST-POINT"))
    )
    (comp (ref "U4")
      (value "FT232RQ")
      (footprint "eagle-import:QFN32")
      (libsource (lib "eagle-import") (part "FT232RQ"))
    )
  )
  (nets
    (net (code "1") (name "ACC_CS") (class "Default")
      (node (ref "TP7") (pin "P$1") (pinfunction "TESTPOINT_P$1") (pintype "bidirectional"))
      (node (ref "U10") (pin "AC17") (pinfunction "P0.21_AC17") (pintype "bidirectional"))
      (node (ref "U6") (pin "2") (pinfunction "CS_2") (pintype "bidirectional"))
    )
    (net (code "2") (name "ACC_INT1") (class "Default")
      (node (ref "TP18") (pin "P$1") (pinfunction "TESTPOINT_P$1") (pintype "bidirectional"))
      (node (ref "U10") (pin "AD16") (pinfunction "P0.20_AD16") (pintype "bidirectional"))
      (node (ref "U6") (pin "12") (pinfunction "INT1_12") (pintype "bidirectional"))
    )
    (net (code "3") (name "ACC_INT2") (class "Default")
      (node (ref "TP19") (pin "P$1") (pinfunction "TESTPOINT_P$1") (pintype "bidirectional"))
      (node (ref "U10") (pin "AD18") (pinfunction "P0.22_AD18") (pintype "bidirectional"))
      (node (ref "U6") (pin "11") (pinfunction "INT2_11") (pintype "bidirectional"))
    )
    (net (code "4") (name "DBG_RX") (class "Default")
      (node (ref "SJ5") (pin "2") (pinfunction "2_2") (pintype "passive"))
      (node (ref "U10") (pin "G1") (pinfunction "P0.26_G1") (pintype "bidirectional"))
    )
    (net (code "5") (name "DBG_TX") (class "Default")
      (node (ref "SJ4") (pin "2") (pinfunction "2_2") (pintype "passive"))
      (node (ref "U10") (pin "H2") (pinfunction "P0.27_H2") (pintype "bidirectional"))
    )
    (net (code "6") (name "GND") (class "Default")
      (node (ref "A2") (pin "S2") (pinfunction "GND_S2") (pintype "bidirectional"))
      (node (ref "BT1") (pin "-") (pinfunction "-_-") (pintype "bidirectional"))
      (node (ref "BT2") (pin "GND") (pinfunction "-_GND") (pintype "bidirectional"))
      (node (ref "BT3") (pin "GND") (pinfunction "-_GND") (pintype "bidirectional"))
      (node (ref "BT4") (pin "-") (pinfunction "-_-") (pintype "bidirectional"))
      (node (ref "C1") (pin "2") (pinfunction "2_2") (pintype "bidirectional"))
      (node (ref "C10") (pin "2") (pinfunction "2_2") (pintype "bidirectional"))
      (node (ref "C11") (pin "2") (pinfunction "2_2") (pintype "bidirectional"))
      (node (ref "C12") (pin "2") (pinfunction "2_2") (pintype "bidirectional"))
      (node (ref "C13") (pin "2") (pinfunction "2_2") (pintype "bidirectional"))
      (node (ref "C14") (pin "2") (pinfunction "2_2") (pintype "bidirectional"))
      (node (ref "C15") (pin "2") (pinfunction "2_2") (pintype "bidirectional"))
      (node (ref "C16") (pin "2") (pinfunction "2_2") (pintype "bidirectional"))
      (node (ref "C17") (pin "2") (pinfunction "2_2") (pintype "bidirectional"))
      (node (ref "C18") (pin "2") (pinfunction "2_2") (pintype "bidirectional"))
      (node (ref "C19") (pin "2") (pinfunction "2_2") (pintype "bidirectional"))
      (node (ref "C2") (pin "2") (pinfunction "2_2") (pintype "bidirectional"))
      (node (ref "C20") (pin "2") (pinfunction "2_2") (pintype "bidirectional"))
      (node (ref "C21") (pin "2") (pinfunction "2_2") (pintype "bidirectional"))
      (node (ref "C22") (pin "2") (pinfunction "2_2") (pintype "bidirectional"))
      (node (ref "C23") (pin "2") (pinfunction "2_2") (pintype "bidirectional"))
      (node (ref "C24") (pin "2") (pinfunction "2_2") (pintype "bidirectional"))
      (node (ref "C25") (pin "2") (pinfunction "2_2") (pintype "bidirectional"))
      (node (ref "C26") (pin "2") (pinfunction "2_2") (pintype "bidirectional"))
      (node (ref "C27") (pin "2") (pinfunction "2_2") (pintype "bidirectional"))
      (node (ref "C28") (pin "2") (pinfunction "2_2") (pintype "bidirectional"))
      (node (ref "C29") (pin "2") (pinfunction "2_2") (pintype "bidirectional"))
      (node (ref "C3") (pin "1") (pinfunction "1_1") (pintype "bidirectional"))
      (node (ref "C30") (pin "2") (pinfunction "2_2") (pintype "bidirectional"))
      (node (ref "C31") (pin "2") (pinfunction "2_2") (pintype "bidirectional"))
      (node (ref "C32") (pin "2") (pinfunction "2_2") (pintype "bidirectional"))
      (node (ref "C33") (pin "2") (pinfunction "2_2") (pintype "bidirectional"))
      (node (ref "C34") (pin "2") (pinfunction "2_2") (pintype "bidirectional"))
      (node (ref "C4") (pin "1") (pinfunction "1_1") (pintype "bidirectional"))
      (node (ref "C5") (pin "1") (pinfunction "1_1") (pintype "bidirectional"))
      (node (ref "C6") (pin "1") (pinfunction "1_1") (pintype "bidirectional"))
      (node (ref "C7") (pin "2") (pinfunction "2_2") (pintype "bidirectional"))
      (node (ref "C8") (pin "2") (pinfunction "2_2") (pintype "bidirectional"))
      (node (ref "C9") (pin "2") (pinfunction "2_2") (pintype "bidirectional"))
      (node (ref "D1") (pin "-") (pinfunction "V-_-") (pintype "bidirectional"))
      (node (ref "J1") (pin "5") (pinfunction "GND_5") (pintype "bidirectional"))
      (node (ref "J5") (pin "5") (pinfunction "GND_5") (pintype "bidirectional"))
      (node (ref "R13") (pin "1") (pinfunction "1_1") (pintype "passive"))
      (node (ref "R18") (pin "1") (pinfunction "1_1") (pintype "passive"))
      (node (ref "R21") (pin "1") (pinfunction "1_1") (pintype "passive"))
      (node (ref "S1") (pin "P$1") (pinfunction "P$1_P$1") (pintype "passive"))
      (node (ref "S1") (pin "P$3") (pinfunction "P$1_P$3") (pintype "passive"))
      (node (ref "TP27") (pin "P$1") (pinfunction "TESTPOINT_P$1") (pintype "bidirectional"))
      (node (ref "U1") (pin "GND") (pinfunction "VSS_GND") (pintype "bidirectional"))
      (node (ref "U10") (pin "AD2") (pinfunction "VBUS_AD2") (pintype "bidirectional"))
      (node (ref "U10") (pin "B7") (pinfunction "VSS_B7") (pintype "bidirectional"))
      (node (ref "U10") (pin "F23") (pinfunction "VSS_PA_F23") (pintype "bidirectional"))
      (node (ref "U10") (pin "GND") (pinfunction "VSS_GND") (pintype "bidirectional"))
      (node (ref "U11") (pin "2") (pinfunction "GND_2") (pintype "bidirectional"))
      (node (ref "U12") (pin "3") (pinfunction "GND_3") (pintype "bidirectional"))
      (node (ref "U2") (pin "1") (pinfunction "GND_1") (pintype "bidirectional"))
      (node (ref "U2") (pin "15") (pinfunction "GND_15") (pintype "bidirectional"))
      (node (ref "U2") (pin "16") (pinfunction "GND_16") (pintype "bidirectional"))
      (node (ref "U2") (pin "17") (pinfunction "GND_17") (pintype "bidirectional"))
      (node (ref "U2") (pin "5") (pinfunction "~{EN}_5") (pintype "bidirectional"))
      (node (ref "U2") (pin "6") (pinfunction "GND_6") (pintype "bidirectional"))
      (node (ref "U2") (pin "PAD") (pinfunction "GND_PAD") (pintype "bidirectional"))
      (node (ref "U3") (pin "GND") (pinfunction "GND_GND") (pintype "bidirectional"))
      (node (ref "U4") (pin "17") (pinfunction "GND_17") (pintype "power_in"))
      (node (ref "U4") (pin "20") (pinfunction "GND_20") (pintype "power_in"))
      (node (ref "U4") (pin "24") (pinfunction "GND_24") (pintype "power_in"))
      (node (ref "U4") (pin "26") (pinfunction "TEST_26") (pintype "input"))
      (node (ref "U4") (pin "4") (pinfunction "GND_4") (pintype "power_in"))
      (node (ref "U6") (pin "5") (pinfunction "GND_5") (pintype "bidirectional"))
      (node (ref "U6") (pin "6") (pinfunction "GND_6") (pintype "bidirectional"))
      (node (ref "U6") (pin "7") (pinfunction "GND_7") (pintype "bidirectional"))
      (node (ref "U6") (pin "8") (pinfunction "GND_8") (pintype "bidirectional"))
      (node (ref "U7") (pin "3") (pinfunction "GND_3") (pintype "bidirectional"))
      (node (ref "U8") (pin "2") (pinfunction "GND_2") (pintype "bidirectional"))
      (node (ref "U8") (pin "3") (pinfunction "A0_3") (pintype "bidirectional"))
      (node (ref "U8") (pin "EP") (pinfunction "GND_EP") (pintype "bidirectional"))
      (node (ref "U9") (pin "4") (pinfunction "GND_4") (pintype "bidirectional"))
      (node (ref "X1") (pin "2") (pinfunction "GND_2") (pintype "bidirectional"))
      (node (ref "X1") (pin "4") (pinfunction "GND_4") (pintype "bidirectional"))
    )
    (net (code "7") (name "LBST") (class "Default")
      (node (ref "L5") (pin "P$1") (pinfunction "1_P$1") (pintype "bidirectional"))
      (node (ref "U10") (pin "AC15") (pinfunction "P0.19_AC15") (pintype "bidirectional"))
      (node (ref "U2") (pin "20") (pinfunction "LBST_20") (pintype "bidirectional"))
    )
    (net (code "8") (name "LED_BLUE") (class "Default")
      (node (ref "R3") (pin "2") (pinfunction "2_2") (pintype "passive"))
      (node (ref "U10") (pin "K2") (pinfunction "P0.05/AIN3_K2") (pintype "bidirectional"))
    )
    (net (code "9") (name "LED_GREEN") (class "Default")
      (node (ref "R2") (pin "2") (pinfunction "2_2") (pintype "passive"))
      (node (ref "U10") (pin "L1") (pinfunction "P0.06_L1") (pintype "bidirectional"))
    )
    (net (code "10") (name "LED_RED") (class "Default")
      (node (ref "R1") (pin "2") (pinfunction "2_2") (pintype "passive"))
      (node (ref "U10") (pin "J1") (pinfunction "P0.04/AIN2_J1") (pintype "bidirectional"))
    )
    (net (code "11") (name "MISO") (class "Default")
      (node (ref "TP4") (pin "P$1") (pinfunction "TESTPOINT_P$1") (pintype "bidirectional"))
      (node (ref "U1") (pin "6") (pinfunction "SDO_6") (pintype "bidirectional"))
      (node (ref "U10") (pin "R1") (pinfunction "P1.09_R1") (pintype "bidirectional"))
      (node (ref "U6") (pin "3") (pinfunction "MISO/SA0_3") (pintype "bidirectional"))
    )
    (net (code "12") (name "MOSI") (class "Default")
      (node (ref "TP5") (pin "P$1") (pinfunction "TESTPOINT_P$1") (pintype "bidirectional"))
      (node (ref "U1") (pin "9") (pinfunction "SDI_9") (pintype "bidirectional"))
      (node (ref "U10") (pin "N1") (pinfunction "P0.08_N1") (pintype "bidirectional"))
      (node (ref "U6") (pin "4") (pinfunction "MOSI/SDA_4") (pintype "bidirectional"))
    )
    (net (code "13") (name "Net-(A2-ANTENNA)") (class "Default")
      (node (ref "A2") (pin "S1") (pinfunction "ANTENNA_S1") (pintype "bidirectional"))
      (node (ref "C2") (pin "1") (pinfunction "1_1") (pintype "bidirectional"))
      (node (ref "L1") (pin "1") (pinfunction "1_1") (pintype "bidirectional"))
    )
    (net (code "14") (name "Net-(D2-B)") (class "Default")
      (node (ref "D2") (pin "3") (pinfunction "B_3") (pintype "output"))
      (node (ref "R3") (pin "1") (pinfunction "1_1") (pintype "passive"))
    )
    (net (code "15") (name "Net-(D2-G)") (class "Default")
      (node (ref "D2") (pin "4") (pinfunction "G_4") (pintype "output"))
      (node (ref "R2") (pin "1") (pinfunction "1_1") (pintype "passive"))
    )
    (net (code "16") (name "Net-(D2-R)") (class "Default")
      (node (ref "D2") (pin "2") (pinfunction "R_2") (pintype "output"))
      (node (ref "R1") (pin "1") (pinfunction "1_1") (pintype "passive"))
    )
    (net (code "17") (name "Net-(J5-D+)") (class "Default")
      (node (ref "J5") (pin "3") (pinfunction "D+_3") (pintype "bidirectional"))
      (node (ref "U4") (pin "14") (pinfunction "USBDP_14") (pintype "bidirectional"))
    )
    (net (code "18") (name "Net-(J5-D-)") (class "Default")
      (node (ref "J5") (pin "2") (pinfunction "D-_2") (pintype "bidirectional"))
      (node (ref "U4") (pin "15") (pinfunction "USBDM_15") (pintype "bidirectional"))
    )
    (net (code "19") (name "Net-(L2-Pad2)") (class "Default")
      (node (ref "L2") (pin "2") (pinfunction "2_2") (pintype "bidirectional"))
      (node (ref "L4") (pin "1") (pinfunction "1_1") (pintype "bidirectional"))
    )
    (net (code "20") (name "Net-(Q1A-D)") (class "Default")
      (node (ref "Q1") (pin "6") (pinfunction "D_6") (pintype "passive"))
      (node (ref "U9") (pin "3") (pinfunction "SCL_3") (pintype "bidirectional"))
    )
    (net (code "21") (name "Net-(Q1B-D)") (class "Default")
      (node (ref "Q1") (pin "3") (pinfunction "D_3") (pintype "passive"))
      (node (ref "U9") (pin "2") (pinfunction "SDA_2") (pintype "bidirectional"))
    )
    (net (code "22") (name "Net-(Q2A-D)") (class "Default")
      (node (ref "Q2") (pin "6") (pinfunction "D_6") (pintype "passive"))
      (node (ref "U11") (pin "6") (pinfunction "SCL_6") (pintype "bidirectional"))
    )
    (net (code "23") (name "Net-(Q2B-D)") (class "Default")
      (node (ref "Q2") (pin "3") (pinfunction "D_3") (pintype "passive"))
      (node (ref "U11") (pin "1") (pinfunction "SDA_1") (pintype "bidirectional"))
    )
    (net (code "24") (name "Net-(Q3A-D)") (class "Default")
      (node (ref "Q3") (pin "6") (pinfunction "D_6") (pintype "passive"))
      (node (ref "U8") (pin "5") (pinfunction "SCL_5") (pintype "bidirectional"))
    )
    (net (code "25") (name "Net-(Q3B-D)") (class "Default")
      (node (ref "Q3") (pin "3") (pinfunction "D_3") (pintype "passive"))
      (node (ref "U8") (pin "6") (pinfunction "SDA_6") (pintype "bidirectional"))
    )
    (net (code "26") (name "Net-(Q4A-D)") (class "Default")
      (node (ref "Q4") (pin "6") (pinfunction "D_6") (pintype "passive"))
      (node (ref "U12") (pin "2") (pinfunction "SCL_2") (pintype "bidirectional"))
    )
    (net (code "27") (name "Net-(Q4B-D)") (class "Default")
      (node (ref "Q4") (pin "3") (pinfunction "D_3") (pintype "passive"))
      (node (ref "U12") (pin "6") (pinfunction "SDA_6") (pintype "bidirectional"))
    )
    (net (code "28") (name "Net-(Q5A-D)") (class "Default")
      (node (ref "C11") (pin "1") (pinfunction "1_1") (pintype "bidirectional"))
      (node (ref "C28") (pin "1") (pinfunction "1_1") (pintype "bidirectional"))
      (node (ref "Q5") (pin "6") (pinfunction "D_6") (pintype "passive"))
      (node (ref "U2") (pin "19") (pinfunction "VSTOR_19") (pintype "bidirectional"))
      (node (ref "U2") (pin "3") (pinfunction "VOC_SAMP_3") (pintype "bidirectional"))
    )
    (net (code "29") (name "Net-(Q5A-G)") (class "Default")
      (node (ref "Q5") (pin "2") (pinfunction "G_2") (pintype "passive"))
      (node (ref "Q5") (pin "5") (pinfunction "G_5") (pintype "passive"))
      (node (ref "U2") (pin "9") (pinfunction "~{VBAT_SEC_ON}_9") (pintype "bidirectional"))
    )
    (net (code "30") (name "Net-(Q5A-S)") (class "Default")
      (node (ref "Q5") (pin "1") (pinfunction "S_1") (pintype "passive"))
      (node (ref "Q5") (pin "4") (pinfunction "S_4") (pintype "passive"))
    )
    (net (code "31") (name "Net-(Q6A-G)") (class "Default")
      (node (ref "Q6") (pin "2") (pinfunction "G_2") (pintype "passive"))
      (node (ref "Q6") (pin "5") (pinfunction "G_5") (pintype "passive"))
      (node (ref "U2") (pin "10") (pinfunction "~{VBAT_PRI_ON}_10") (pintype "bidirectional"))
    )
    (net (code "32") (name "Net-(Q6A-S)") (class "Default")
      (node (ref "Q6") (pin "1") (pinfunction "S_1") (pintype "passive"))
      (node (ref "Q6") (pin "4") (pinfunction "S_4") (pintype "passive"))
    )
    (net (code "33") (name "Net-(Q7A-D)") (class "Default")
      (node (ref "Q7") (pin "6") (pinfunction "D_6") (pintype "passive"))
      (node (ref "U12") (pin "1") (pinfunction "VDD_1") (pintype "bidirectional"))
    )
    (net (code "34") (name "Net-(Q7B-D)") (class "Default")
      (node (ref "Q7") (pin "3") (pinfunction "D_3") (pintype "passive"))
      (node (ref "U8") (pin "1") (pinfunction "VCC_1") (pintype "bidirectional"))
    )
    (net (code "35") (name "Net-(Q8A-D)") (class "Default")
      (node (ref "Q8") (pin "6") (pinfunction "D_6") (pintype "passive"))
      (node (ref "U9") (pin "1") (pinfunction "VDD_1") (pintype "bidirectional"))
    )
    (net (code "36") (name "Net-(Q8B-D)") (class "Default")
      (node (ref "Q8") (pin "3") (pinfunction "D_3") (pintype "passive"))
      (node (ref "U11") (pin "5") (pinfunction "VCC_5") (pintype "bidirectional"))
    )
    (net (code "37") (name "Net-(Q10A-D)") (class "Default")
      (node (ref "Q10") (pin "6") (pinfunction "D_6") (pintype "passive"))
      (node (ref "U3") (pin "VCC") (pinfunction "VCC_VCC") (pintype "bidirectional"))
    )
    (net (code "38") (name "Net-(U1-AF)") (class "Default")
      (node (ref "C7") (pin "1") (pinfunction "1_1") (pintype "bidirectional"))
      (node (ref "U1") (pin "14") (pinfunction "AF_14") (pintype "bidirectional"))
    )
    (net (code "39") (name "Net-(U1-XI)") (class "Default")
      (node (ref "C33") (pin "1") (pinfunction "1_1") (pintype "bidirectional"))
      (node (ref "U1") (pin "16") (pinfunction "XI_16") (pintype "bidirectional"))
      (node (ref "X4") (pin "1") (pinfunction "1_1") (pintype "bidirectional"))
    )
    (net (code "40") (name "Net-(U1-XO)") (class "Default")
      (node (ref "C34") (pin "1") (pinfunction "1_1") (pintype "bidirectional"))
      (node (ref "U1") (pin "15") (pinfunction "XO_15") (pintype "bidirectional"))
      (node (ref "X4") (pin "2") (pinfunction "2_2") (pintype "bidirectional"))
    )
    (net (code "41") (name "Net-(U1-~{EXTR})") (class "Default")
      (node (ref "R10") (pin "1") (pinfunction "1_1") (pintype "passive"))
      (node (ref "S1") (pin "P$2") (pinfunction "P$2_P$2") (pintype "passive"))
      (node (ref "S1") (pin "P$4") (pinfunction "P$2_P$4") (pintype "passive"))
      (node (ref "U1") (pin "3") (pinfunction "~{EXTR}_3") (pintype "bidirectional"))
    )
    (net (code "42") (name "Net-(U2-OK_HYST)") (class "Default")
      (node (ref "R17") (pin "2") (pinfunction "2_2") (pintype "passive"))
      (node (ref "R4") (pin "1") (pinfunction "1_1") (pintype "passive"))
      (node (ref "U2") (pin "11") (pinfunction "OK_HYST_11") (pintype "bidirectional"))
    )
    (net (code "43") (name "Net-(U2-OK_PROG)") (class "Default")
      (node (ref "R17") (pin "1") (pinfunction "1_1") (pintype "passive"))
      (node (ref "R18") (pin "2") (pinfunction "2_2") (pintype "passive"))
      (node (ref "U2") (pin "12") (pinfunction "OK_PROG_12") (pintype "bidirectional"))
    )
    (net (code "44") (name "Net-(U2-VBAT_OV)") (class "Default")
      (node (ref "R14") (pin "1") (pinfunction "1_1") (pintype "passive"))
      (node (ref "R21") (pin "2") (pinfunction "2_2") (pintype "passive"))
      (node (ref "U2") (pin "7") (pinfunction "VBAT_OV_7") (pintype "bidirectional"))
    )
    (net (code "45") (name "Net-(U2-VRDIV)") (class "Default")
      (node (ref "R14") (pin "2") (pinfunction "2_2") (pintype "passive"))
      (node (ref "R4") (pin "2") (pinfunction "2_2") (pintype "passive"))
      (node (ref "U2") (pin "8") (pinfunction "VRDIV_8") (pintype "bidirectional"))
    )
    (net (code "46") (name "Net-(U2-VREF_SAMP)") (class "Default")
      (node (ref "C10") (pin "1") (pinfunction "1_1") (pintype "bidirectional"))
      (node (ref "U2") (pin "4") (pinfunction "VREF_SAMP_4") (pintype "bidirectional"))
    )
    (net (code "47") (name "Net-(U4-3V3OUT)") (class "Default")
      (node (ref "C21") (pin "1") (pinfunction "1_1") (pintype "bidirectional"))
      (node (ref "U4") (pin "16") (pinfunction "3V3OUT_16") (pintype "output"))
    )
    (net (code "48") (name "Net-(U4-RXD)") (class "Default")
      (node (ref "SJ4") (pin "1") (pinfunction "1_1") (pintype "passive"))
      (node (ref "U4") (pin "2") (pinfunction "RXD_2") (pintype "input"))
    )
    (net (code "49") (name "Net-(U4-TXD)") (class "Default")
      (node (ref "SJ5") (pin "1") (pinfunction "1_1") (pintype "passive"))
      (node (ref "U4") (pin "30") (pinfunction "TXD_30") (pintype "output"))
    )
    (net (code "50") (name "Net-(U4-VCCIO)") (class "Default")
      (node (ref "SJ2") (pin "2") (pinfunction "2_2") (pintype "passive"))
      (node (ref "U4") (pin "1") (pinfunction "VCCIO_1") (pintype "power_in"))
    )
    (net (code "51") (name "Net-(U4-~{RESET})") (class "Default")
      (node (ref "SJ3") (pin "2") (pinfunction "2_2") (pintype "passive"))
      (node (ref "U4") (pin "18") (pinfunction "~{RESET}_18") (pintype "input"))
    )
    (net (code "52") (name "Net-(U7-EN)") (class "Default")
      (node (ref "R22") (pin "1") (pinfunction "1_1") (pintype "passive"))
      (node (ref "U7") (pin "6") (pinfunction "EN_6") (pintype "bidirectional"))
    )
    (net (code "53") (name "Net-(U7-SEL)") (class "Default")
      (node (ref "R13") (pin "2") (pinfunction "2_2") (pintype "passive"))
      (node (ref "U7") (pin "4") (pinfunction "SEL_4") (pintype "bidirectional"))
    )
    (net (code "54") (name "Net-(U10-ANT)") (class "Default")
      (node (ref "C1") (pin "1") (pinfunction "1_1") (pintype "bidirectional"))
      (node (ref "L1") (pin "2") (pinfunction "2_2") (pintype "bidirectional"))
      (node (ref "U10") (pin "H23") (pinfunction "ANT_H23") (pintype "bidirectional"))
    )
    (net (code "55") (name "Net-(U10-DCC)") (class "Default")
      (node (ref "L4") (pin "2") (pinfunction "2_2") (pintype "bidirectional"))
      (node (ref "U10") (pin "B3") (pinfunction "DCC_B3") (pintype "bidirectional"))
    )
    (net (code "56") (name "Net-(U10-DEC1)") (class "Default")
      (node (ref "C15") (pin "1") (pinfunction "1_1") (pintype "bidirectional"))
      (node (ref "U10") (pin "C1") (pinfunction "DEC1_C1") (pintype "bidirectional"))
    )
    (net (code "57") (name "Net-(U10-DEC3)") (class "Default")
      (node (ref "C8") (pin "1") (pinfunction "1_1") (pintype "bidirectional"))
      (node (ref "U10") (pin "D23") (pinfunction "DEC3_D23") (pintype "bidirectional"))
    )
    (net (code "58") (name "Net-(U10-DEC4)") (class "Default")
      (node (ref "C12") (pin "1") (pinfunction "1_1") (pintype "bidirectional"))
      (node (ref "C23") (pin "1") (pinfunction "1_1") (pintype "bidirectional"))
      (node (ref "L2") (pin "1") (pinfunction "1_1") (pintype "bidirectional"))
      (node (ref "U10") (pin "B5") (pinfunction "DEC4_B5") (pintype "bidirectional"))
      (node (ref "U10") (pin "E24") (pinfunction "DEC6_E24") (pintype "bidirectional"))
    )
    (net (code "59") (name "Net-(U10-DEC5)") (class "Default")
      (node (ref "C9") (pin "1") (pinfunction "1_1") (pintype "bidirectional"))
      (node (ref "U10") (pin "N24") (pinfunction "DEC5_N24") (pintype "bidirectional"))
    )
    (net (code "60") (name "Net-(U10-P0.00{slash}XL1)") (class "Default")
      (node (ref "C6") (pin "2") (pinfunction "2_2") (pintype "bidirectional"))
      (node (ref "U10") (pin "D2") (pinfunction "P0.00/XL1_D2") (pintype "bidirectional"))
      (node (ref "X3") (pin "A") (pinfunction "1_A") (pintype "bidirectional"))
    )
    (net (code "61") (name "Net-(U10-P0.01{slash}XL2)") (class "Default")
      (node (ref "C5") (pin "2") (pinfunction "2_2") (pintype "bidirectional"))
      (node (ref "U10") (pin "F2") (pinfunction "P0.01/XL2_F2") (pintype "bidirectional"))
      (node (ref "X3") (pin "B") (pinfunction "2_B") (pintype "bidirectional"))
    )
    (net (code "62") (name "Net-(U10-XC1)") (class "Default")
      (node (ref "C3") (pin "2") (pinfunction "2_2") (pintype "bidirectional"))
      (node (ref "U10") (pin "B24") (pinfunction "XC1_B24") (pintype "bidirectional"))
      (node (ref "X1") (pin "3") (pinfunction "2_3") (pintype "bidirectional"))
    )
    (net (code "63") (name "Net-(U10-XC2)") (class "Default")
      (node (ref "C4") (pin "2") (pinfunction "2_2") (pintype "bidirectional"))
      (node (ref "U10") (pin "A23") (pinfunction "XC2_A23") (pintype "bidirectional"))
      (node (ref "X1") (pin "1") (pinfunction "1_1") (pintype "bidirectional"))
    )
    (net (code "64") (name "PIR_OUT") (class "Default")
      (node (ref "TP22") (pin "P$1") (pinfunction "TESTPOINT_P$1") (pintype "bidirectional"))
      (node (ref "U10") (pin "AC11") (pinfunction "P0.16_AC11") (pintype "bidirectional"))
      (node (ref "U3") (pin "OUT") (pinfunction "OUT_OUT") (pintype "bidirectional"))
    )
    (net (code "65") (name "RTC_CS") (class "Default")
      (node (ref "TP6") (pin "P$1") (pinfunction "TESTPOINT_P$1") (pintype "bidirectional"))
      (node (ref "U1") (pin "12") (pinfunction "~{CS}_12") (pintype "bidirectional"))
      (node (ref "U10") (pin "B17") (pinfunction "P1.12_B17") (pintype "bidirectional"))
    )
    (net (code "66") (name "SCK") (class "Default")
      (node (ref "TP3") (pin "P$1") (pinfunction "TESTPOINT_P$1") (pintype "bidirectional"))
      (node (ref "U1") (pin "7") (pinfunction "SCL_7") (pintype "bidirectional"))
      (node (ref "U10") (pin "U1") (pinfunction "P0.12_U1") (pintype "bidirectional"))
      (node (ref "U6") (pin "1") (pinfunction "SCL/SPC_1") (pintype "bidirectional"))
    )
    (net (code "67") (name "SCL") (class "Default")
      (node (ref "Q1") (pin "1") (pinfunction "S_1") (pintype "passive"))
      (node (ref "Q2") (pin "1") (pinfunction "S_1") (pintype "passive"))
      (node (ref "Q3") (pin "1") (pinfunction "S_1") (pintype "passive"))
      (node (ref "Q4") (pin "1") (pinfunction "S_1") (pintype "passive"))
      (node (ref "R6") (pin "1") (pinfunction "1_1") (pintype "passive"))
      (node (ref "TP2") (pin "P$1") (pinfunction "TESTPOINT_P$1") (pintype "bidirectional"))
      (node (ref "U10") (pin "AC9") (pinfunction "P0.14_AC9") (pintype "bidirectional"))
    )
    (net (code "68") (name "SDA") (class "Default")
      (node (ref "Q1") (pin "4") (pinfunction "S_4") (pintype "passive"))
      (node (ref "Q2") (pin "4") (pinfunction "S_4") (pintype "passive"))
      (node (ref "Q3") (pin "4") (pinfunction "S_4") (pintype "passive"))
      (node (ref "Q4") (pin "4") (pinfunction "S_4") (pintype "passive"))
      (node (ref "R7") (pin "1") (pinfunction "1_1") (pintype "passive"))
      (node (ref "TP1") (pin "P$1") (pinfunction "TESTPOINT_P$1") (pintype "bidirectional"))
      (node (ref "U10") (pin "AD10") (pinfunction "P0.15_AD10") (pintype "bidirectional"))
    )
    (net (code "69") (name "SW") (class "Default")
      (node (ref "L3") (pin "P$2") (pinfunction "2_P$2") (pintype "bidirectional"))
      (node (ref "TP25") (pin "P$1") (pinfunction "TESTPOINT_P$1") (pintype "bidirectional"))
      (node (ref "U10") (pin "AD8") (pinfunction "P0.13_AD8") (pintype "bidirectional"))
      (node (ref "U7") (pin "2") (pinfunction "LX_2") (pintype "bidirectional"))
    )
    (net (code "70") (name "SWDCLK") (class "Default")
      (node (ref "J1") (pin "4") (pinfunction "SWDCLK_4") (pintype "bidirectional"))
      (node (ref "U10") (pin "AA24") (pinfunction "SWDCLK_AA24") (pintype "bidirectional"))
    )
    (net (code "71") (name "SWDIO") (class "Default")
      (node (ref "J1") (pin "2") (pinfunction "SWDIO_2") (pintype "bidirectional"))
      (node (ref "U10") (pin "AC24") (pinfunction "SWDIO_AC24") (pintype "bidirectional"))
    )
    (net (code "72") (name "USB_5V") (class "Default")
      (node (ref "J5") (pin "1") (pinfunction "+5V_1") (pintype "bidirectional"))
      (node (ref "U4") (pin "19") (pinfunction "VCC_19") (pintype "power_in"))
    )
    (net (code "73") (name "VBAT") (class "Default")
      (node (ref "BT2") (pin "POS1") (pinfunction "+_POS1") (pintype "bidirectional"))
      (node (ref "BT2") (pin "POS2") (pinfunction "+_POS2") (pintype "bidirectional"))
      (node (ref "BT2") (pin "POS3") (pinfunction "+_POS3") (pintype "bidirectional"))
      (node (ref "BT2") (pin "POS4") (pinfunction "+_POS4") (pintype "bidirectional"))
      (node (ref "BT3") (pin "POS1") (pinfunction "+_POS1") (pintype "bidirectional"))
      (node (ref "BT3") (pin "POS2") (pinfunction "+_POS2") (pintype "bidirectional"))
      (node (ref "BT3") (pin "POS3") (pinfunction "+_POS3") (pintype "bidirectional"))
      (node (ref "BT3") (pin "POS4") (pinfunction "+_POS4") (pintype "bidirectional"))
      (node (ref "BT4") (pin "+") (pinfunction "+_+") (pintype "bidirectional"))
      (node (ref "Q6") (pin "6") (pinfunction "D_6") (pintype "passive"))
      (node (ref "U1") (pin "5") (pinfunction "VBAT_5") (pintype "bidirectional"))
      (node (ref "U10") (pin "A10") (pinfunction "P0.29/AIN5_A10") (pintype "bidirectional"))
      (node (ref "U2") (pin "14") (pinfunction "VBAT_PRI_14") (pintype "bidirectional"))
    )
    (net (code "74") (name "VBAT_OK") (class "Default")
      (node (ref "U10") (pin "R24") (pinfunction "P1.06_R24") (pintype "bidirectional"))
      (node (ref "U2") (pin "13") (pinfunction "VBAT_OK_13") (pintype "bidirectional"))
    )
    (net (code "75") (name "VCC") (class "Default")
      (node (ref "C13") (pin "1") (pinfunction "1_1") (pintype "bidirectional"))
      (node (ref "C14") (pin "1") (pinfunction "1_1") (pintype "bidirectional"))
      (node (ref "C16") (pin "1") (pinfunction "1_1") (pintype "bidirectional"))
      (node (ref "C17") (pin "1") (pinfunction "1_1") (pintype "bidirectional"))
      (node (ref "C18") (pin "1") (pinfunction "1_1") (pintype "bidirectional"))
      (node (ref "C19") (pin "1") (pinfunction "1_1") (pintype "bidirectional"))
      (node (ref "C20") (pin "1") (pinfunction "1_1") (pintype "bidirectional"))
      (node (ref "C22") (pin "1") (pinfunction "1_1") (pintype "bidirectional"))
      (node (ref "C24") (pin "1") (pinfunction "1_1") (pintype "bidirectional"))
      (node (ref "C25") (pin "1") (pinfunction "1_1") (pintype "bidirectional"))
      (node (ref "C26") (pin "1") (pinfunction "1_1") (pintype "bidirectional"))
      (node (ref "C27") (pin "1") (pinfunction "1_1") (pintype "bidirectional"))
      (node (ref "C31") (pin "1") (pinfunction "1_1") (pintype "bidirectional"))
      (node (ref "C32") (pin "1") (pinfunction "1_1") (pintype "bidirectional"))
      (node (ref "D2") (pin "1") (pinfunction "VDD_1") (pintype "bidirectional"))
      (node (ref "J1") (pin "1") (pinfunction "VCC_1") (pintype "bidirectional"))
      (node (ref "Q10") (pin "1") (pinfunction "S_1") (pintype "passive"))
      (node (ref "Q7") (pin "1") (pinfunction "S_1") (pintype "passive"))
      (node (ref "Q7") (pin "4") (pinfunction "S_4") (pintype "passive"))
      (node (ref "Q8") (pin "1") (pinfunction "S_1") (pintype "passive"))
      (node (ref "Q8") (pin "4") (pinfunction "S_4") (pintype "passive"))
      (node (ref "R10") (pin "2") (pinfunction "2_2") (pintype "passive"))
      (node (ref "R11") (pin "2") (pinfunction "2_2") (pintype "passive"))
      (node (ref "R12") (pin "2") (pinfunction "2_2") (pintype "passive"))
      (node (ref "R23") (pin "2") (pinfunction "2_2") (pintype "passive"))
      (node (ref "R24") (pin "2") (pinfunction "2_2") (pintype "passive"))
      (node (ref "R25") (pin "2") (pinfunction "2_2") (pintype "passive"))
      (node (ref "R26") (pin "2") (pinfunction "2_2") (pintype "passive"))
      (node (ref "R27") (pin "2") (pinfunction "2_2") (pintype "passive"))
      (node (ref "R6") (pin "2") (pinfunction "2_2") (pintype "passive"))
      (node (ref "R7") (pin "2") (pinfunction "2_2") (pintype "passive"))
      (node (ref "R8") (pin "2") (pinfunction "2_2") (pintype "passive"))
      (node (ref "R9") (pin "2") (pinfunction "2_2") (pintype "passive"))
      (node (ref "SJ2") (pin "1") (pinfunction "1_1") (pintype "passive"))
      (node (ref "TP26") (pin "P$1") (pinfunction "TESTPOINT_P$1") (pintype "bidirectional"))
      (node (ref "U1") (pin "13") (pinfunction "VCC_13") (pintype "bidirectional"))
      (node (ref "U10") (pin "A22") (pinfunction "VDD_A22") (pintype "bidirectional"))
      (node (ref "U10") (pin "AD14") (pinfunction "VDD_AD14") (pintype "bidirectional"))
      (node (ref "U10") (pin "AD23") (pinfunction "VDD_AD23") (pintype "bidirectional"))
      (node (ref "U10") (pin "B1") (pinfunction "VDD_B1") (pintype "bidirectional"))
      (node (ref "U10") (pin "W1") (pinfunction "VDD_W1") (pintype "bidirectional"))
      (node (ref "U10") (pin "Y2") (pinfunction "VDDH_Y2") (pintype "bidirectional"))
      (node (ref "U6") (pin "10") (pinfunction "VDD_IO_10") (pintype "bidirectional"))
      (node (ref "U6") (pin "9") (pinfunction "VCC_9") (pintype "bidirectional"))
      (node (ref "U7") (pin "1") (pinfunction "OUT_1") (pintype "bidirectional"))
    )
    (net (code "76") (name "VSEC") (class "Default")
      (node (ref "BT1") (pin "+") (pinfunction "+_+") (pintype "bidirectional"))
      (node (ref "TP24") (pin "P$1") (pinfunction "TESTPOINT_P$1") (pintype "bidirectional"))
      (node (ref "U10") (pin "A8") (pinfunction "P0.31/AIN7_A8") (pintype "bidirectional"))
      (node (ref "U2") (pin "18") (pinfunction "VBAT_SEC_18") (pintype "bidirectional"))
    )
    (net (code "77") (name "VSOL") (class "Default")
      (node (ref "C29") (pin "1") (pinfunction "1_1") (pintype "bidirectional"))
      (node (ref "D1") (pin "+") (pinfunction "V+_+") (pintype "bidirectional"))
      (node (ref "L5") (pin "P$2") (pinfunction "2_P$2") (pintype "bidirectional"))
      (node (ref "TP23") (pin "P$1") (pinfunction "TESTPOINT_P$1") (pintype "bidirectional"))
      (node (ref "U10") (pin "B9") (pinfunction "P0.30/AIN6_B9") (pintype "bidirectional"))
      (node (ref "U2") (pin "2") (pinfunction "VIN_DC_2") (pintype "bidirectional"))
    )
    (net (code "78") (name "VSW") (class "Default")
      (node (ref "C30") (pin "1") (pinfunction "1_1") (pintype "bidirectional"))
      (node (ref "L3") (pin "P$1") (pinfunction "1_P$1") (pintype "bidirectional"))
      (node (ref "Q5") (pin "3") (pinfunction "D_3") (pintype "passive"))
      (node (ref "Q6") (pin "3") (pinfunction "D_3") (pintype "passive"))
      (node (ref "R22") (pin "2") (pinfunction "2_2") (pintype "passive"))
      (node (ref "U7") (pin "5") (pinfunction "IN_5") (pintype "bidirectional"))
    )
    (net (code "79") (name "WDI") (class "Default")
      (node (ref "R12") (pin "1") (pinfunction "1_1") (pintype "passive"))
      (node (ref "TP16") (pin "P$1") (pinfunction "TESTPOINT_P$1") (pintype "bidirectional"))
      (node (ref "U1") (pin "2") (pinfunction "WDI_2") (pintype "bidirectional"))
      (node (ref "U10") (pin "A12") (pinfunction "P0.02/AIN0_A12") (pintype "bidirectional"))
    )
    (net (code "80") (name "unconnected-(J1-SWO-Pad6)") (class "Default")
      (node (ref "J1") (pin "6") (pinfunction "SWO_6") (pintype "bidirectional"))
    )
    (net (code "81") (name "unconnected-(J5-ID-Pad4)") (class "Default")
      (node (ref "J5") (pin "4") (pinfunction "ID_4") (pintype "bidirectional"))
    )
    (net (code "82") (name "unconnected-(U1-EXTI-Pad10)") (class "Default")
      (node (ref "U1") (pin "10") (pinfunction "EXTI_10") (pintype "bidirectional"))
    )
    (net (code "83") (name "unconnected-(U4-CBUS0-Pad22)") (class "Default")
      (node (ref "U4") (pin "22") (pinfunction "CBUS0_22") (pintype "bidirectional"))
    )
    (net (code "84") (name "unconnected-(U4-CBUS1-Pad21)") (class "Default")
      (node (ref "U4") (pin "21") (pinfunction "CBUS1_21") (pintype "bidirectional"))
    )
    (net (code "85") (name "unconnected-(U4-CBUS2-Pad10)") (class "Default")
      (node (ref "U4") (pin "10") (pinfunction "CBUS2_10") (pintype "bidirectional"))
    )
    (net (code "86") (name "unconnected-(U4-CBUS3-Pad11)") (class "Default")
      (node (ref "U4") (pin "11") (pinfunction "CBUS3_11") (pintype "bidirectional"))
    )
    (net (code "87") (name "unconnected-(U4-CBUS4-Pad9)") (class "Default")
      (node (ref "U4") (pin "9") (pinfunction "CBUS4_9") (pintype "bidirectional"))
    )
    (net (code "88") (name "unconnected-(U4-OSCI-Pad27)") (class "Default")
      (node (ref "U4") (pin "27") (pinfunction "OSCI_27") (pintype "input"))
    )
    (net (code "89") (name "unconnected-(U4-OSCO-Pad28)") (class "Default")
      (node (ref "U4") (pin "28") (pinfunction "OSCO_28") (pintype "output"))
    )
    (net (code "90") (name "unconnected-(U4-~{CTS}-Pad8)") (class "Default")
      (node (ref "U4") (pin "8") (pinfunction "~{CTS}_8") (pintype "input"))
    )
    (net (code "91") (name "unconnected-(U4-~{DCD}-Pad7)") (class "Default")
      (node (ref "U4") (pin "7") (pinfunction "~{DCD}_7") (pintype "input"))
    )
    (net (code "92") (name "unconnected-(U4-~{DSR}-Pad6)") (class "Default")
      (node (ref "U4") (pin "6") (pinfunction "~{DSR}_6") (pintype "input"))
    )
    (net (code "93") (name "unconnected-(U4-~{DTR}-Pad31)") (class "Default")
      (node (ref "U4") (pin "31") (pinfunction "~{DTR}_31") (pintype "output"))
    )
    (net (code "94") (name "unconnected-(U4-~{RI}-Pad3)") (class "Default")
      (node (ref "U4") (pin "3") (pinfunction "~{RI}_3") (pintype "input"))
    )
    (net (code "95") (name "unconnected-(U4-~{RTS}-Pad32)") (class "Default")
      (node (ref "U4") (pin "32") (pinfunction "~{RTS}_32") (pintype "output"))
    )
    (net (code "96") (name "unconnected-(U10-D+-PadAD6)") (class "Default")
      (node (ref "U10") (pin "AD6") (pinfunction "D+_AD6") (pintype "bidirectional"))
    )
    (net (code "97") (name "unconnected-(U10-D--PadAD4)") (class "Default")
      (node (ref "U10") (pin "AD4") (pinfunction "D-_AD4") (pintype "bidirectional"))
    )
    (net (code "98") (name "unconnected-(U10-DCCH-PadAB2)") (class "Default")
      (node (ref "U10") (pin "AB2") (pinfunction "DCCH_AB2") (pintype "bidirectional"))
    )
    (net (code "99") (name "unconnected-(U10-DEC2-PadA18)") (class "Default")
      (node (ref "U10") (pin "A18") (pinfunction "DEC2_A18") (pintype "bidirectional"))
    )
    (net (code "100") (name "unconnected-(U10-DECUSB-PadAC5)") (class "Default")
      (node (ref "U10") (pin "AC5") (pinfunction "DECUSB_AC5") (pintype "bidirectional"))
    )
    (net (code "101") (name "unconnected-(U10-P0.03{slash}AIN1-PadB13)") (class "Default")
      (node (ref "U10") (pin "B13") (pinfunction "P0.03/AIN1_B13") (pintype "bidirectional"))
    )
    (net (code "102") (name "unconnected-(U10-P0.07-PadM2)") (class "Default")
      (node (ref "U10") (pin "M2") (pinfunction "P0.07_M2") (pintype "bidirectional"))
    )
    (net (code "103") (name "unconnected-(U10-P0.09{slash}NFC1-PadL24)") (class "Default")
      (node (ref "U10") (pin "L24") (pinfunction "P0.09/NFC1_L24") (pintype "bidirectional"))
    )
    (net (code "104") (name "unconnected-(U10-P0.10{slash}NFC2-PadJ24)") (class "Default")
      (node (ref "U10") (pin "J24") (pinfunction "P0.10/NFC2_J24") (pintype "bidirectional"))
    )
    (net (code "105") (name "unconnected-(U10-P0.11-PadT2)") (class "Default")
      (node (ref "U10") (pin "T2") (pinfunction "P0.11_T2") (pintype "bidirectional"))
    )
    (net (code "106") (name "unconnected-(U10-P0.28{slash}AIN4-PadB11)") (class "Default")
      (node (ref "U10") (pin "B11") (pinfunction "P0.28/AIN4_B11") (pintype "bidirectional"))
    )
    (net (code "107") (name "unconnected-(U10-P1.01-PadY23)") (class "Default")
      (node (ref "U10") (pin "Y23") (pinfunction "P1.01_Y23") (pintype "bidirectional"))
    )
    (net (code "108") (name "unconnected-(U10-P1.02-PadW24)") (class "Default")
      (node (ref "U10") (pin "W24") (pinfunction "P1.02_W24") (pintype "bidirectional"))
    )
    (net (code "109") (name "unconnected-(U10-P1.03-PadV23)") (class "Default")
      (node (ref "U10") (pin "V23") (pinfunction "P1.03_V23") (pintype "bidirectional"))
    )
    (net (code "110") (name "unconnected-(U10-P1.04-PadU24)") (class "Default")
      (node (ref "U10") (pin "U24") (pinfunction "P1.04_U24") (pintype "bidirectional"))
    )
    (net (code "111") (name "unconnected-(U10-P1.05-PadT23)") (class "Default")
      (node (ref "U10") (pin "T23") (pinfunction "P1.05_T23") (pintype "bidirectional"))
    )
    (net (code "112") (name "unconnected-(U10-P1.07-PadP23)") (class "Default")
      (node (ref "U10") (pin "P23") (pinfunction "P1.07_P23") (pintype "bidirectional"))
    )
    (net (code "113") (name "unconnected-(U10-P1.08-PadP2)") (class "Default")
      (node (ref "U10") (pin "P2") (pinfunction "P1.08_P2") (pintype "bidirectional"))
    )
    (net (code "114") (name "~{CLR_EN}") (class "Default")
      (node (ref "Q4") (pin "2") (pinfunction "G_2") (pintype "passive"))
      (node (ref "Q4") (pin "5") (pinfunction "G_5") (pintype "passive"))
      (node (ref "Q7") (pin "2") (pinfunction "G_2") (pintype "passive"))
      (node (ref "R23") (pin "1") (pinfunction "1_1") (pintype "passive"))
      (node (ref "TP9") (pin "P$1") (pinfunction "TESTPOINT_P$1") (pintype "bidirectional"))
      (node (ref "U10") (pin "AC21") (pinfunction "P0.25_AC21") (pintype "bidirectional"))
    )
    (net (code "115") (name "~{CLR_INT}") (class "Default")
      (node (ref "R8") (pin "1") (pinfunction "1_1") (pintype "passive"))
      (node (ref "TP20") (pin "P$1") (pinfunction "TESTPOINT_P$1") (pintype "bidirectional"))
      (node (ref "U10") (pin "AC19") (pinfunction "P0.23_AC19") (pintype "bidirectional"))
      (node (ref "U12") (pin "5") (pinfunction "INT_5") (pintype "bidirectional"))
    )
    (net (code "116") (name "~{HUM_EN}") (class "Default")
      (node (ref "Q2") (pin "2") (pinfunction "G_2") (pintype "passive"))
      (node (ref "Q2") (pin "5") (pinfunction "G_5") (pintype "passive"))
      (node (ref "Q8") (pin "5") (pinfunction "G_5") (pintype "passive"))
      (node (ref "R26") (pin "1") (pinfunction "1_1") (pintype "passive"))
      (node (ref "TP12") (pin "P$1") (pinfunction "TESTPOINT_P$1") (pintype "bidirectional"))
      (node (ref "U10") (pin "A20") (pinfunction "P1.10_A20") (pintype "bidirectional"))
    )
    (net (code "117") (name "~{LT_EN}") (class "Default")
      (node (ref "Q3") (pin "2") (pinfunction "G_2") (pintype "passive"))
      (node (ref "Q3") (pin "5") (pinfunction "G_5") (pintype "passive"))
      (node (ref "Q7") (pin "5") (pinfunction "G_5") (pintype "passive"))
      (node (ref "R24") (pin "1") (pinfunction "1_1") (pintype "passive"))
      (node (ref "TP10") (pin "P$1") (pinfunction "TESTPOINT_P$1") (pintype "bidirectional"))
      (node (ref "U10") (pin "AD20") (pinfunction "P0.24_AD20") (pintype "bidirectional"))
    )
    (net (code "118") (name "~{LT_INT}") (class "Default")
      (node (ref "R9") (pin "1") (pinfunction "1_1") (pintype "passive"))
      (node (ref "TP21") (pin "P$1") (pinfunction "TESTPOINT_P$1") (pintype "bidirectional"))
      (node (ref "U10") (pin "AD22") (pinfunction "P1.00_AD22") (pintype "bidirectional"))
      (node (ref "U8") (pin "4") (pinfunction "~{INT}_4") (pintype "bidirectional"))
    )
    (net (code "119") (name "~{PIR_EN}") (class "Default")
      (node (ref "Q10") (pin "2") (pinfunction "G_2") (pintype "passive"))
      (node (ref "R27") (pin "1") (pinfunction "1_1") (pintype "passive"))
      (node (ref "TP11") (pin "P$1") (pinfunction "TESTPOINT_P$1") (pintype "bidirectional"))
      (node (ref "U10") (pin "AD12") (pinfunction "P0.17_AD12") (pintype "bidirectional"))
    )
    (net (code "120") (name "~{PR_EN}") (class "Default")
      (node (ref "Q1") (pin "2") (pinfunction "G_2") (pintype "passive"))
      (node (ref "Q1") (pin "5") (pinfunction "G_5") (pintype "passive"))
      (node (ref "Q8") (pin "2") (pinfunction "G_2") (pintype "passive"))
      (node (ref "R25") (pin "1") (pinfunction "1_1") (pintype "passive"))
      (node (ref "TP8") (pin "P$1") (pinfunction "TESTPOINT_P$1") (pintype "bidirectional"))
      (node (ref "U10") (pin "B19") (pinfunction "P1.11_B19") (pintype "bidirectional"))
    )
    (net (code "121") (name "~{RST}") (class "Default")
      (node (ref "J1") (pin "3") (pinfunction "~{RESET}_3") (pintype "bidirectional"))
      (node (ref "R11") (pin "1") (pinfunction "1_1") (pintype "passive"))
      (node (ref "SJ3") (pin "1") (pinfunction "1_1") (pintype "passive"))
      (node (ref "TP17") (pin "P$1") (pinfunction "TESTPOINT_P$1") (pintype "bidirectional"))
      (node (ref "U1") (pin "1") (pinfunction "~{RST}_1") (pintype "bidirectional"))
      (node (ref "U10") (pin "AC13") (pinfunction "P0.18_AC13") (pintype "bidirectional"))
    )
    (net (code "122") (name "~{RTC_IRQ1}") (class "Default")
      (node (ref "TP13") (pin "P$1") (pinfunction "TESTPOINT_P$1") (pintype "bidirectional"))
      (node (ref "U1") (pin "11") (pinfunction "FOUT/~{IRQ1}_11") (pintype "bidirectional"))
      (node (ref "U10") (pin "A16") (pinfunction "P1.13_A16") (pintype "bidirectional"))
    )
    (net (code "123") (name "~{RTC_IRQ2}") (class "Default")
      (node (ref "TP14") (pin "P$1") (pinfunction "TESTPOINT_P$1") (pintype "bidirectional"))
      (node (ref "U1") (pin "4") (pinfunction "~{IRQ2}_4") (pintype "bidirectional"))
      (node (ref "U10") (pin "B15") (pinfunction "P1.14_B15") (pintype "bidirectional"))
    )
    (net (code "124") (name "~{RTC_IRQ3}") (class "Default")
      (node (ref "TP15") (pin "P$1") (pinfunction "TESTPOINT_P$1") (pintype "bidirectional"))
      (node (ref "U1") (pin "8") (pinfunction "CLKOUT/~{IRQ3}_8") (pintype "bidirectional"))
      (node (ref "U10") (pin "A14") (pinfunction "P1.15_A14") (pintype "bidirectional"))
    )
  )
)
